# ArtFire.net
KiCad netlist of a schematic drawn in Altium Designer
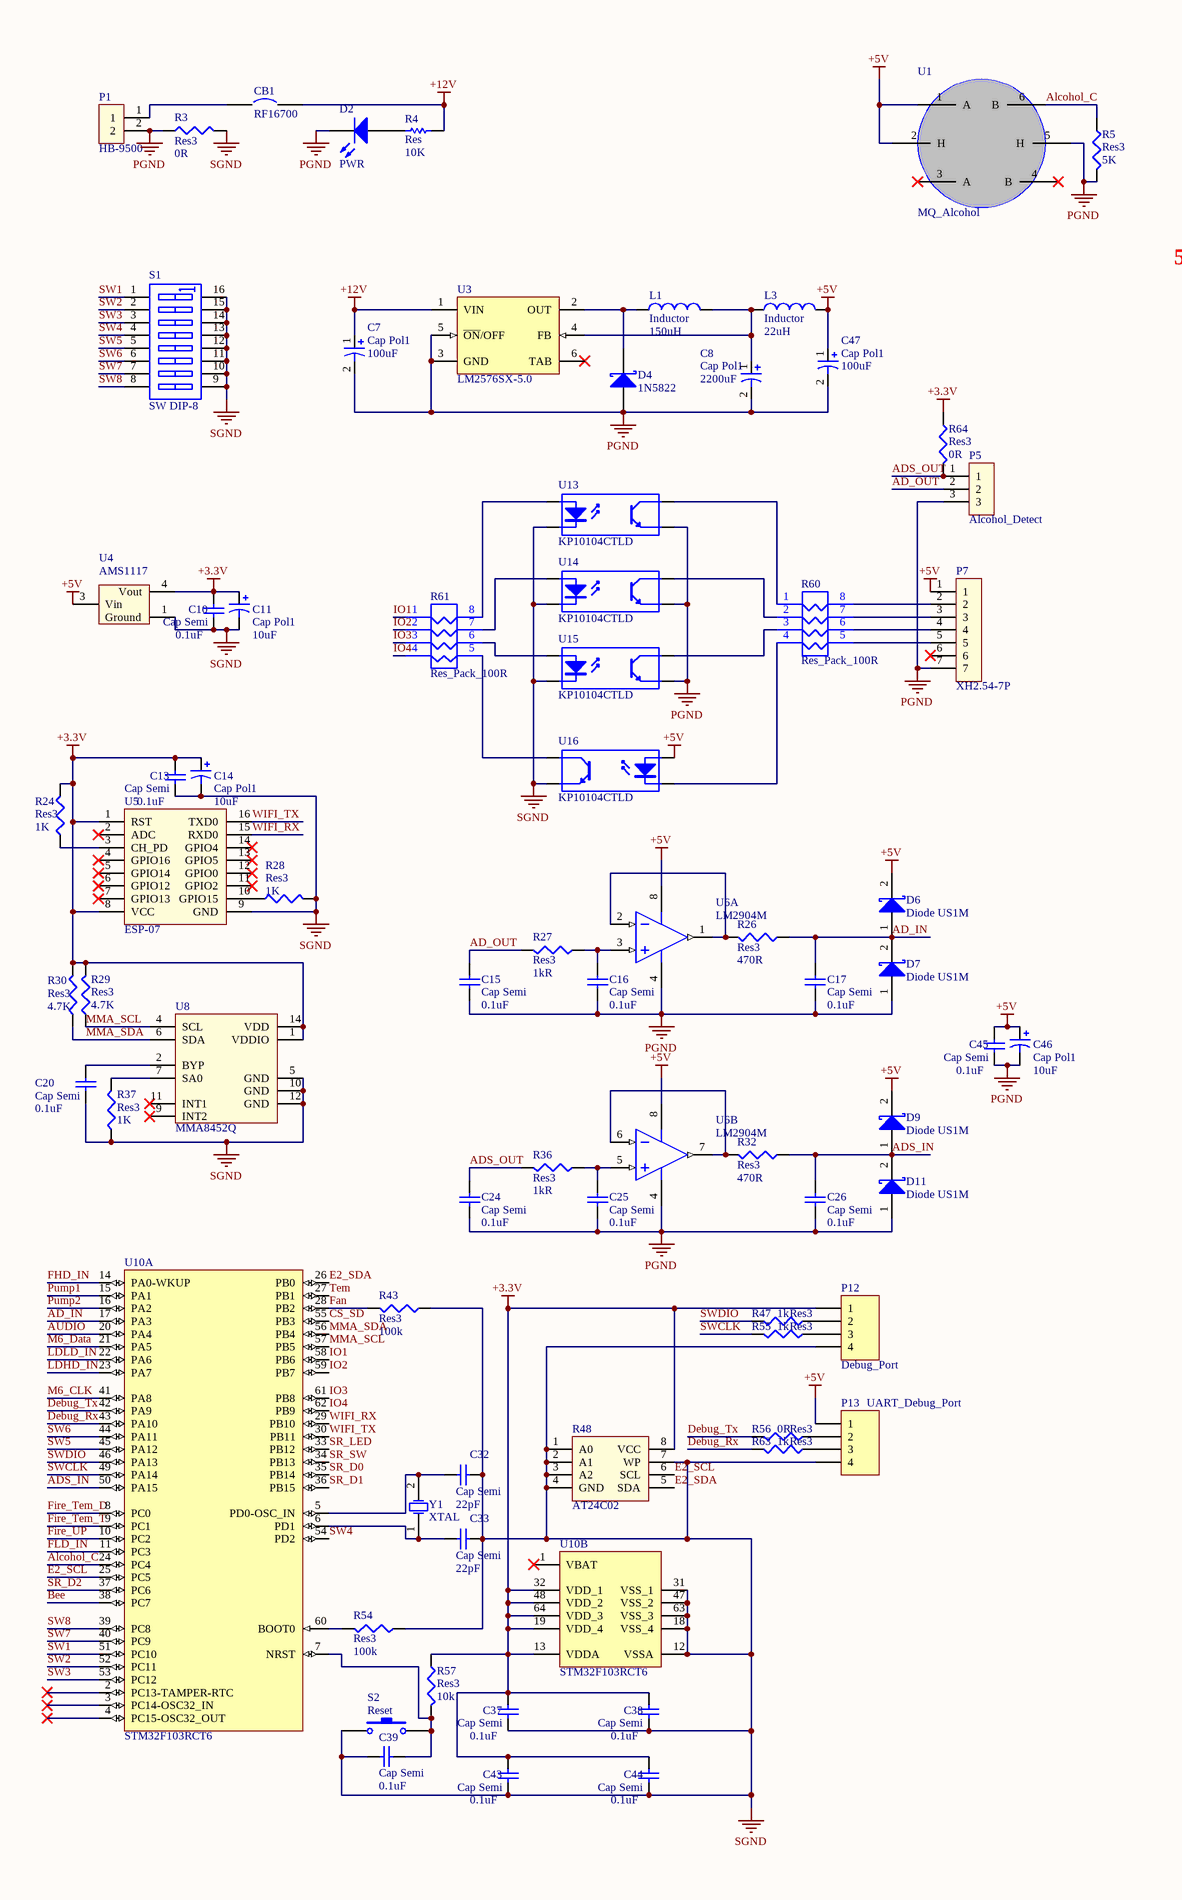
[diagram p0: ArtFire.SchDoc, left]
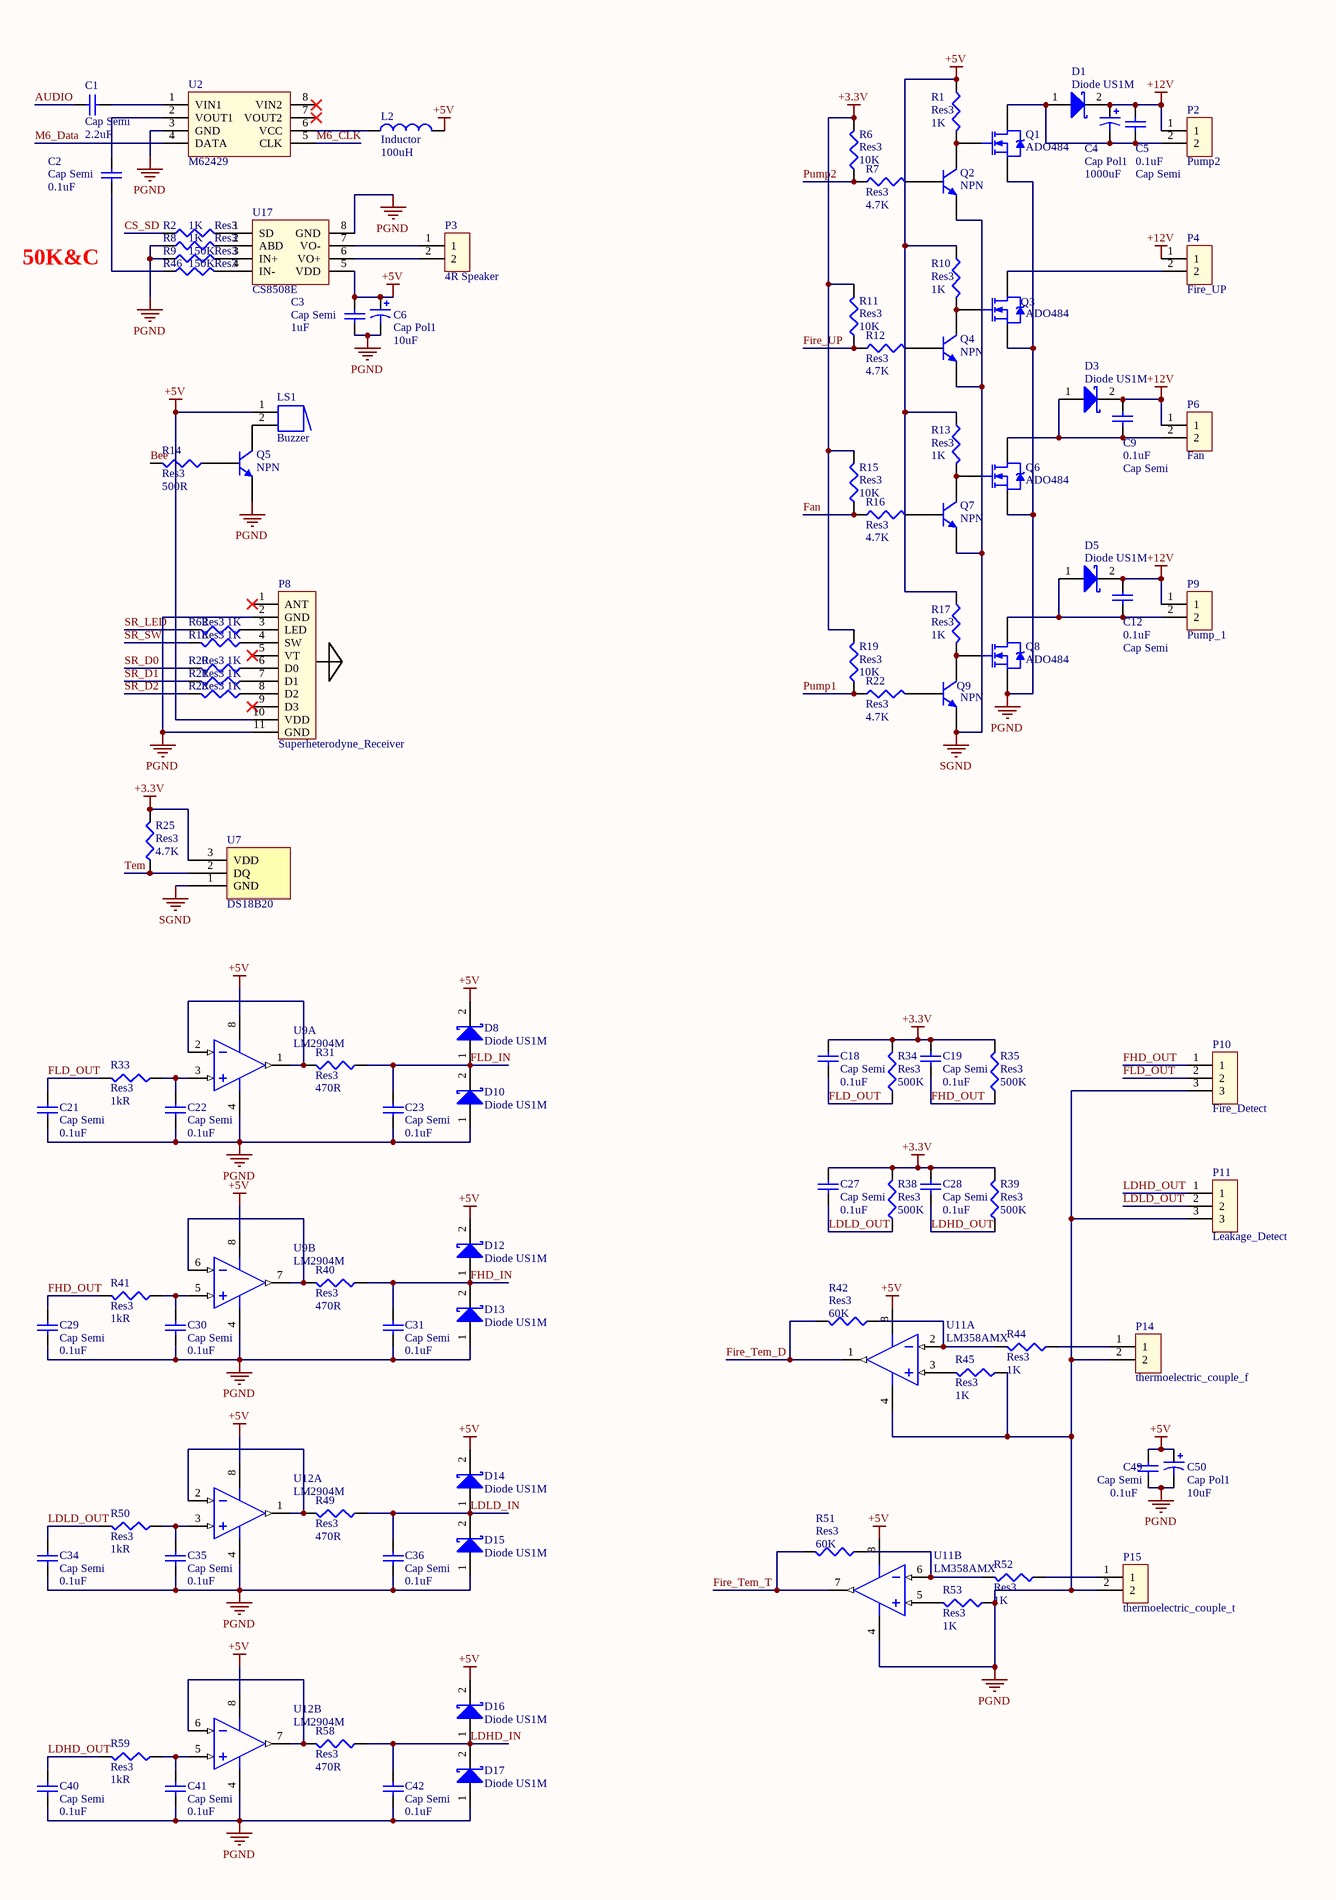
[diagram p1: ArtFire.SchDoc, right]

(export (version "E")
  (design (tool "Eeschema 10.0.6"))
  (components
    (comp (ref "C1")
      (value "Cap Semi")
      (footprint "6-0805_N")
      (description "Capacitor (Semiconductor SIM Model)")
      (fields (field (name "ALTIUM_VALUE") "2.2uF") (field (name "PUBLISHER") "Altium Limited"))
      (libsource (lib "Miscellaneous Devices") (part "Cap Semi"))
    )
    (comp (ref "C2")
      (value "Cap Semi")
      (footprint "6-0805_N")
      (description "Capacitor (Semiconductor SIM Model)")
      (fields (field (name "ALTIUM_VALUE") "0.1uF") (field (name "PUBLISHER") "Altium Limited"))
      (libsource (lib "Miscellaneous Devices") (part "Cap Semi"))
    )
    (comp (ref "C3")
      (value "Cap Semi")
      (footprint "6-0805_N")
      (description "Capacitor (Semiconductor SIM Model)")
      (fields (field (name "ALTIUM_VALUE") "1uF") (field (name "PUBLISHER") "Altium Limited"))
      (libsource (lib "Miscellaneous Devices") (part "Cap Semi"))
    )
    (comp (ref "C4")
      (value "Cap Pol1")
      (footprint "CAP_10*10MM")
      (description "Polarized Capacitor (Radial)")
      (fields (field (name "ALTIUM_VALUE") "1000uF") (field (name "PUBLISHER") "Altium Limited"))
      (libsource (lib "Miscellaneous Devices") (part "Cap Pol1"))
    )
    (comp (ref "C5")
      (value "Cap Semi")
      (footprint "6-0805_N")
      (description "Capacitor (Semiconductor SIM Model)")
      (fields (field (name "ALTIUM_VALUE") "0.1uF") (field (name "PUBLISHER") "Altium Limited"))
      (libsource (lib "Miscellaneous Devices") (part "Cap Semi"))
    )
    (comp (ref "C6")
      (value "Cap Pol1")
      (footprint "Cap_5*4mm")
      (description "Polarized Capacitor (Radial)")
      (fields (field (name "ALTIUM_VALUE") "10uF") (field (name "PUBLISHER") "Altium Limited"))
      (libsource (lib "Miscellaneous Devices") (part "Cap Pol1"))
    )
    (comp (ref "C7")
      (value "Cap Pol1")
      (footprint "CAP_6.3*5.4MM")
      (description "Polarized Capacitor (Radial)")
      (fields (field (name "ALTIUM_VALUE") "100uF") (field (name "PUBLISHER") "Altium Limited"))
      (libsource (lib "") (part "Cap Pol1_1"))
    )
    (comp (ref "C8")
      (value "Cap Pol1")
      (footprint "CAP10_17")
      (description "Polarized Capacitor (Radial)")
      (fields (field (name "ALTIUM_VALUE") "2200uF") (field (name "PUBLISHER") "Altium Limited"))
      (libsource (lib "") (part "Cap Pol1_1"))
    )
    (comp (ref "C9")
      (value "Cap Semi")
      (footprint "6-0805_N")
      (description "Capacitor (Semiconductor SIM Model)")
      (fields (field (name "ALTIUM_VALUE") "0.1uF") (field (name "PUBLISHER") "Altium Limited"))
      (libsource (lib "Miscellaneous Devices") (part "Cap Semi"))
    )
    (comp (ref "C10")
      (value "Cap Semi")
      (footprint "6-0805_N")
      (description "Capacitor (Semiconductor SIM Model)")
      (fields (field (name "ALTIUM_VALUE") "0.1uF") (field (name "PUBLISHER") "Altium Limited"))
      (libsource (lib "Miscellaneous Devices") (part "Cap Semi"))
    )
    (comp (ref "C11")
      (value "Cap Pol1")
      (footprint "Cap_5*4mm")
      (description "Polarized Capacitor (Radial)")
      (fields (field (name "ALTIUM_VALUE") "10uF") (field (name "PUBLISHER") "Altium Limited"))
      (libsource (lib "Miscellaneous Devices") (part "Cap Pol1"))
    )
    (comp (ref "C12")
      (value "Cap Semi")
      (footprint "6-0805_N")
      (description "Capacitor (Semiconductor SIM Model)")
      (fields (field (name "ALTIUM_VALUE") "0.1uF") (field (name "PUBLISHER") "Altium Limited"))
      (libsource (lib "Miscellaneous Devices") (part "Cap Semi"))
    )
    (comp (ref "C13")
      (value "Cap Semi")
      (footprint "6-0805_N")
      (description "Capacitor (Semiconductor SIM Model)")
      (fields (field (name "ALTIUM_VALUE") "0.1uF") (field (name "PUBLISHER") "Altium Limited"))
      (libsource (lib "Miscellaneous Devices") (part "Cap Semi"))
    )
    (comp (ref "C14")
      (value "Cap Pol1")
      (footprint "Cap_5*4mm")
      (description "Polarized Capacitor (Radial)")
      (fields (field (name "ALTIUM_VALUE") "10uF") (field (name "PUBLISHER") "Altium Limited"))
      (libsource (lib "Miscellaneous Devices") (part "Cap Pol1"))
    )
    (comp (ref "C15")
      (value "Cap Semi")
      (footprint "6-0805_N")
      (description "Capacitor (Semiconductor SIM Model)")
      (fields (field (name "ALTIUM_VALUE") "0.1uF") (field (name "PUBLISHER") "Altium Limited"))
      (libsource (lib "Miscellaneous Devices") (part "Cap Semi"))
    )
    (comp (ref "C16")
      (value "Cap Semi")
      (footprint "6-0805_N")
      (description "Capacitor (Semiconductor SIM Model)")
      (fields (field (name "ALTIUM_VALUE") "0.1uF") (field (name "PUBLISHER") "Altium Limited"))
      (libsource (lib "Miscellaneous Devices") (part "Cap Semi"))
    )
    (comp (ref "C17")
      (value "Cap Semi")
      (footprint "6-0805_N")
      (description "Capacitor (Semiconductor SIM Model)")
      (fields (field (name "ALTIUM_VALUE") "0.1uF") (field (name "PUBLISHER") "Altium Limited"))
      (libsource (lib "Miscellaneous Devices") (part "Cap Semi"))
    )
    (comp (ref "C18")
      (value "Cap Semi")
      (footprint "6-0805_N")
      (description "Capacitor (Semiconductor SIM Model)")
      (fields (field (name "ALTIUM_VALUE") "0.1uF") (field (name "PUBLISHER") "Altium Limited"))
      (libsource (lib "Miscellaneous Devices") (part "Cap Semi"))
    )
    (comp (ref "C19")
      (value "Cap Semi")
      (footprint "6-0805_N")
      (description "Capacitor (Semiconductor SIM Model)")
      (fields (field (name "ALTIUM_VALUE") "0.1uF") (field (name "PUBLISHER") "Altium Limited"))
      (libsource (lib "Miscellaneous Devices") (part "Cap Semi"))
    )
    (comp (ref "C20")
      (value "Cap Semi")
      (footprint "6-0805_N")
      (description "Capacitor (Semiconductor SIM Model)")
      (fields (field (name "ALTIUM_VALUE") "0.1uF") (field (name "PUBLISHER") "Altium Limited"))
      (libsource (lib "Miscellaneous Devices") (part "Cap Semi"))
    )
    (comp (ref "C21")
      (value "Cap Semi")
      (footprint "6-0805_N")
      (description "Capacitor (Semiconductor SIM Model)")
      (fields (field (name "ALTIUM_VALUE") "0.1uF") (field (name "PUBLISHER") "Altium Limited"))
      (libsource (lib "Miscellaneous Devices") (part "Cap Semi"))
    )
    (comp (ref "C22")
      (value "Cap Semi")
      (footprint "6-0805_N")
      (description "Capacitor (Semiconductor SIM Model)")
      (fields (field (name "ALTIUM_VALUE") "0.1uF") (field (name "PUBLISHER") "Altium Limited"))
      (libsource (lib "Miscellaneous Devices") (part "Cap Semi"))
    )
    (comp (ref "C23")
      (value "Cap Semi")
      (footprint "6-0805_N")
      (description "Capacitor (Semiconductor SIM Model)")
      (fields (field (name "ALTIUM_VALUE") "0.1uF") (field (name "PUBLISHER") "Altium Limited"))
      (libsource (lib "Miscellaneous Devices") (part "Cap Semi"))
    )
    (comp (ref "C24")
      (value "Cap Semi")
      (footprint "6-0805_N")
      (description "Capacitor (Semiconductor SIM Model)")
      (fields (field (name "ALTIUM_VALUE") "0.1uF") (field (name "PUBLISHER") "Altium Limited"))
      (libsource (lib "Miscellaneous Devices") (part "Cap Semi"))
    )
    (comp (ref "C25")
      (value "Cap Semi")
      (footprint "6-0805_N")
      (description "Capacitor (Semiconductor SIM Model)")
      (fields (field (name "ALTIUM_VALUE") "0.1uF") (field (name "PUBLISHER") "Altium Limited"))
      (libsource (lib "Miscellaneous Devices") (part "Cap Semi"))
    )
    (comp (ref "C26")
      (value "Cap Semi")
      (footprint "6-0805_N")
      (description "Capacitor (Semiconductor SIM Model)")
      (fields (field (name "ALTIUM_VALUE") "0.1uF") (field (name "PUBLISHER") "Altium Limited"))
      (libsource (lib "Miscellaneous Devices") (part "Cap Semi"))
    )
    (comp (ref "C27")
      (value "Cap Semi")
      (footprint "6-0805_N")
      (description "Capacitor (Semiconductor SIM Model)")
      (fields (field (name "ALTIUM_VALUE") "0.1uF") (field (name "PUBLISHER") "Altium Limited"))
      (libsource (lib "Miscellaneous Devices") (part "Cap Semi"))
    )
    (comp (ref "C28")
      (value "Cap Semi")
      (footprint "6-0805_N")
      (description "Capacitor (Semiconductor SIM Model)")
      (fields (field (name "ALTIUM_VALUE") "0.1uF") (field (name "PUBLISHER") "Altium Limited"))
      (libsource (lib "Miscellaneous Devices") (part "Cap Semi"))
    )
    (comp (ref "C29")
      (value "Cap Semi")
      (footprint "6-0805_N")
      (description "Capacitor (Semiconductor SIM Model)")
      (fields (field (name "ALTIUM_VALUE") "0.1uF") (field (name "PUBLISHER") "Altium Limited"))
      (libsource (lib "Miscellaneous Devices") (part "Cap Semi"))
    )
    (comp (ref "C30")
      (value "Cap Semi")
      (footprint "6-0805_N")
      (description "Capacitor (Semiconductor SIM Model)")
      (fields (field (name "ALTIUM_VALUE") "0.1uF") (field (name "PUBLISHER") "Altium Limited"))
      (libsource (lib "Miscellaneous Devices") (part "Cap Semi"))
    )
    (comp (ref "C31")
      (value "Cap Semi")
      (footprint "6-0805_N")
      (description "Capacitor (Semiconductor SIM Model)")
      (fields (field (name "ALTIUM_VALUE") "0.1uF") (field (name "PUBLISHER") "Altium Limited"))
      (libsource (lib "Miscellaneous Devices") (part "Cap Semi"))
    )
    (comp (ref "C32")
      (value "Cap Semi")
      (footprint "6-0805_N")
      (description "Capacitor (Semiconductor SIM Model)")
      (fields (field (name "ALTIUM_VALUE") "22pF") (field (name "PUBLISHER") "Altium Limited"))
      (libsource (lib "Miscellaneous Devices") (part "Cap Semi"))
    )
    (comp (ref "C33")
      (value "Cap Semi")
      (footprint "6-0805_N")
      (description "Capacitor (Semiconductor SIM Model)")
      (fields (field (name "ALTIUM_VALUE") "22pF") (field (name "PUBLISHER") "Altium Limited"))
      (libsource (lib "Miscellaneous Devices") (part "Cap Semi"))
    )
    (comp (ref "C34")
      (value "Cap Semi")
      (footprint "6-0805_N")
      (description "Capacitor (Semiconductor SIM Model)")
      (fields (field (name "ALTIUM_VALUE") "0.1uF") (field (name "PUBLISHER") "Altium Limited"))
      (libsource (lib "Miscellaneous Devices") (part "Cap Semi"))
    )
    (comp (ref "C35")
      (value "Cap Semi")
      (footprint "6-0805_N")
      (description "Capacitor (Semiconductor SIM Model)")
      (fields (field (name "ALTIUM_VALUE") "0.1uF") (field (name "PUBLISHER") "Altium Limited"))
      (libsource (lib "Miscellaneous Devices") (part "Cap Semi"))
    )
    (comp (ref "C36")
      (value "Cap Semi")
      (footprint "6-0805_N")
      (description "Capacitor (Semiconductor SIM Model)")
      (fields (field (name "ALTIUM_VALUE") "0.1uF") (field (name "PUBLISHER") "Altium Limited"))
      (libsource (lib "Miscellaneous Devices") (part "Cap Semi"))
    )
    (comp (ref "C37")
      (value "Cap Semi")
      (footprint "6-0805_N")
      (description "Capacitor (Semiconductor SIM Model)")
      (fields (field (name "ALTIUM_VALUE") "0.1uF") (field (name "PUBLISHER") "Altium Limited"))
      (libsource (lib "Miscellaneous Devices") (part "Cap Semi"))
    )
    (comp (ref "C38")
      (value "Cap Semi")
      (footprint "6-0805_N")
      (description "Capacitor (Semiconductor SIM Model)")
      (fields (field (name "ALTIUM_VALUE") "0.1uF") (field (name "PUBLISHER") "Altium Limited"))
      (libsource (lib "Miscellaneous Devices") (part "Cap Semi"))
    )
    (comp (ref "C39")
      (value "Cap Semi")
      (footprint "6-0805_N")
      (description "Capacitor (Semiconductor SIM Model)")
      (fields (field (name "ALTIUM_VALUE") "0.1uF") (field (name "PUBLISHER") "Altium Limited"))
      (libsource (lib "Miscellaneous Devices") (part "Cap Semi"))
    )
    (comp (ref "C40")
      (value "Cap Semi")
      (footprint "6-0805_N")
      (description "Capacitor (Semiconductor SIM Model)")
      (fields (field (name "ALTIUM_VALUE") "0.1uF") (field (name "PUBLISHER") "Altium Limited"))
      (libsource (lib "Miscellaneous Devices") (part "Cap Semi"))
    )
    (comp (ref "C41")
      (value "Cap Semi")
      (footprint "6-0805_N")
      (description "Capacitor (Semiconductor SIM Model)")
      (fields (field (name "ALTIUM_VALUE") "0.1uF") (field (name "PUBLISHER") "Altium Limited"))
      (libsource (lib "Miscellaneous Devices") (part "Cap Semi"))
    )
    (comp (ref "C42")
      (value "Cap Semi")
      (footprint "6-0805_N")
      (description "Capacitor (Semiconductor SIM Model)")
      (fields (field (name "ALTIUM_VALUE") "0.1uF") (field (name "PUBLISHER") "Altium Limited"))
      (libsource (lib "Miscellaneous Devices") (part "Cap Semi"))
    )
    (comp (ref "C43")
      (value "Cap Semi")
      (footprint "6-0805_N")
      (description "Capacitor (Semiconductor SIM Model)")
      (fields (field (name "ALTIUM_VALUE") "0.1uF") (field (name "PUBLISHER") "Altium Limited"))
      (libsource (lib "Miscellaneous Devices") (part "Cap Semi"))
    )
    (comp (ref "C44")
      (value "Cap Semi")
      (footprint "6-0805_N")
      (description "Capacitor (Semiconductor SIM Model)")
      (fields (field (name "ALTIUM_VALUE") "0.1uF") (field (name "PUBLISHER") "Altium Limited"))
      (libsource (lib "Miscellaneous Devices") (part "Cap Semi"))
    )
    (comp (ref "C45")
      (value "Cap Semi")
      (footprint "6-0805_N")
      (description "Capacitor (Semiconductor SIM Model)")
      (fields (field (name "ALTIUM_VALUE") "0.1uF") (field (name "PUBLISHER") "Altium Limited"))
      (libsource (lib "Miscellaneous Devices") (part "Cap Semi"))
    )
    (comp (ref "C46")
      (value "Cap Pol1")
      (footprint "Cap_5*4mm")
      (description "Polarized Capacitor (Radial)")
      (fields (field (name "ALTIUM_VALUE") "10uF") (field (name "PUBLISHER") "Altium Limited"))
      (libsource (lib "Miscellaneous Devices") (part "Cap Pol1"))
    )
    (comp (ref "C47")
      (value "Cap Pol1")
      (footprint "CAP_6.3*5.4MM")
      (description "Polarized Capacitor (Radial)")
      (fields (field (name "ALTIUM_VALUE") "100uF") (field (name "PUBLISHER") "Altium Limited"))
      (libsource (lib "") (part "Cap Pol1_1"))
    )
    (comp (ref "C49")
      (value "Cap Semi")
      (footprint "6-0805_N")
      (description "Capacitor (Semiconductor SIM Model)")
      (fields (field (name "ALTIUM_VALUE") "0.1uF") (field (name "PUBLISHER") "Altium Limited"))
      (libsource (lib "Miscellaneous Devices") (part "Cap Semi"))
    )
    (comp (ref "C50")
      (value "Cap Pol1")
      (footprint "Cap_5*4mm")
      (description "Polarized Capacitor (Radial)")
      (fields (field (name "ALTIUM_VALUE") "10uF") (field (name "PUBLISHER") "Altium Limited"))
      (libsource (lib "Miscellaneous Devices") (part "Cap Pol1"))
    )
    (comp (ref "CB1")
      (value "RF16700")
      (footprint "SPST-2")
      (description "Circuit Breaker")
      (fields (field (name "PUBLISHER") "Altium Limited"))
      (libsource (lib "Miscellaneous Devices") (part "Circuit Breaker"))
    )
    (comp (ref "D1")
      (value "Diode US1M")
      (footprint "US1M")
      (description "Silicon RF Schottky Diode for Mixer Applications in the VHF/UHF Range")
      (fields (field (name "PUBLISHER") "Altium Limited"))
      (libsource (lib "Miscellaneous Devices") (part "Diode BAT17"))
    )
    (comp (ref "D2")
      (value "PWR")
      (footprint "6-0805_N")
      (description "Typical INFRARED GaAs LED")
      (fields (field (name "PUBLISHER") "Altium Limited"))
      (libsource (lib "Miscellaneous Devices") (part "LED0"))
    )
    (comp (ref "D3")
      (value "Diode US1M")
      (footprint "US1M")
      (description "Silicon RF Schottky Diode for Mixer Applications in the VHF/UHF Range")
      (fields (field (name "PUBLISHER") "Altium Limited"))
      (libsource (lib "Miscellaneous Devices") (part "Diode BAT17"))
    )
    (comp (ref "D4")
      (value "1N5822")
      (footprint "US1M")
      (description "Silicon RF Schottky Diode for Mixer Applications in the VHF/UHF Range")
      (fields (field (name "PUBLISHER") "Altium Limited"))
      (libsource (lib "") (part "Diode BAT17_1"))
    )
    (comp (ref "D5")
      (value "Diode US1M")
      (footprint "US1M")
      (description "Silicon RF Schottky Diode for Mixer Applications in the VHF/UHF Range")
      (fields (field (name "PUBLISHER") "Altium Limited"))
      (libsource (lib "Miscellaneous Devices") (part "Diode BAT17"))
    )
    (comp (ref "D6")
      (value "Diode US1M")
      (footprint "US1M")
      (description "Silicon RF Schottky Diode for Mixer Applications in the VHF/UHF Range")
      (fields (field (name "PUBLISHER") "Altium Limited"))
      (libsource (lib "Miscellaneous Devices") (part "Diode BAT17"))
    )
    (comp (ref "D7")
      (value "Diode US1M")
      (footprint "US1M")
      (description "Silicon RF Schottky Diode for Mixer Applications in the VHF/UHF Range")
      (fields (field (name "PUBLISHER") "Altium Limited"))
      (libsource (lib "Miscellaneous Devices") (part "Diode BAT17"))
    )
    (comp (ref "D8")
      (value "Diode US1M")
      (footprint "US1M")
      (description "Silicon RF Schottky Diode for Mixer Applications in the VHF/UHF Range")
      (fields (field (name "PUBLISHER") "Altium Limited"))
      (libsource (lib "Miscellaneous Devices") (part "Diode BAT17"))
    )
    (comp (ref "D9")
      (value "Diode US1M")
      (footprint "US1M")
      (description "Silicon RF Schottky Diode for Mixer Applications in the VHF/UHF Range")
      (fields (field (name "PUBLISHER") "Altium Limited"))
      (libsource (lib "Miscellaneous Devices") (part "Diode BAT17"))
    )
    (comp (ref "D10")
      (value "Diode US1M")
      (footprint "US1M")
      (description "Silicon RF Schottky Diode for Mixer Applications in the VHF/UHF Range")
      (fields (field (name "PUBLISHER") "Altium Limited"))
      (libsource (lib "Miscellaneous Devices") (part "Diode BAT17"))
    )
    (comp (ref "D11")
      (value "Diode US1M")
      (footprint "US1M")
      (description "Silicon RF Schottky Diode for Mixer Applications in the VHF/UHF Range")
      (fields (field (name "PUBLISHER") "Altium Limited"))
      (libsource (lib "Miscellaneous Devices") (part "Diode BAT17"))
    )
    (comp (ref "D12")
      (value "Diode US1M")
      (footprint "US1M")
      (description "Silicon RF Schottky Diode for Mixer Applications in the VHF/UHF Range")
      (fields (field (name "PUBLISHER") "Altium Limited"))
      (libsource (lib "Miscellaneous Devices") (part "Diode BAT17"))
    )
    (comp (ref "D13")
      (value "Diode US1M")
      (footprint "US1M")
      (description "Silicon RF Schottky Diode for Mixer Applications in the VHF/UHF Range")
      (fields (field (name "PUBLISHER") "Altium Limited"))
      (libsource (lib "Miscellaneous Devices") (part "Diode BAT17"))
    )
    (comp (ref "D14")
      (value "Diode US1M")
      (footprint "US1M")
      (description "Silicon RF Schottky Diode for Mixer Applications in the VHF/UHF Range")
      (fields (field (name "PUBLISHER") "Altium Limited"))
      (libsource (lib "Miscellaneous Devices") (part "Diode BAT17"))
    )
    (comp (ref "D15")
      (value "Diode US1M")
      (footprint "US1M")
      (description "Silicon RF Schottky Diode for Mixer Applications in the VHF/UHF Range")
      (fields (field (name "PUBLISHER") "Altium Limited"))
      (libsource (lib "Miscellaneous Devices") (part "Diode BAT17"))
    )
    (comp (ref "D16")
      (value "Diode US1M")
      (footprint "US1M")
      (description "Silicon RF Schottky Diode for Mixer Applications in the VHF/UHF Range")
      (fields (field (name "PUBLISHER") "Altium Limited"))
      (libsource (lib "Miscellaneous Devices") (part "Diode BAT17"))
    )
    (comp (ref "D17")
      (value "Diode US1M")
      (footprint "US1M")
      (description "Silicon RF Schottky Diode for Mixer Applications in the VHF/UHF Range")
      (fields (field (name "PUBLISHER") "Altium Limited"))
      (libsource (lib "Miscellaneous Devices") (part "Diode BAT17"))
    )
    (comp (ref "L1")
      (value "Inductor")
      (footprint "CDRH127")
      (fields (field (name "ALTIUM_VALUE") "150uH") (field (name "PUBLISHER") "Altium Limited"))
      (libsource (lib "Miscellaneous Devices") (part "Inductor"))
    )
    (comp (ref "L2")
      (value "Inductor")
      (footprint "6-0805_L")
      (fields (field (name "ALTIUM_VALUE") "100uH") (field (name "PUBLISHER") "Altium Limited"))
      (libsource (lib "Miscellaneous Devices") (part "Inductor"))
    )
    (comp (ref "L3")
      (value "Inductor")
      (footprint "IND_0630")
      (fields (field (name "ALTIUM_VALUE") "22uH") (field (name "PUBLISHER") "Altium Limited"))
      (libsource (lib "Miscellaneous Devices") (part "Inductor"))
    )
    (comp (ref "LS1")
      (value "Buzzer")
      (footprint "BUZZER")
      (description "Magnetic Transducer Buzzer")
      (fields (field (name "PUBLISHER") "Altium Limited"))
      (libsource (lib "Miscellaneous Devices") (part "Buzzer"))
    )
    (comp (ref "P1")
      (value "HB-9500")
      (footprint "HB-9500")
      (description "High current connector")
      (libsource (lib "Simon'Library") (part "HB-9500"))
    )
    (comp (ref "P2") (value "Pump2") (footprint "CH3.96_2P") (libsource (lib "CH3.96") (part "CH3.96_2P")))
    (comp (ref "P3")
      (value "4R Speaker")
      (footprint "XH2.54-2P")
      (libsource (lib "XH2.54") (part "XH2.54-2P"))
    )
    (comp (ref "P4") (value "Fire_UP") (footprint "KF7.62-2P") (libsource (lib "KF3.96") (part "KF3.96")))
    (comp (ref "P5")
      (value "Alcohol_Detect")
      (footprint "XH2.54-3P")
      (libsource (lib "XH2.54") (part "XH2.54-3P"))
    )
    (comp (ref "P6") (value "Fan") (footprint "XH2.54-2P") (libsource (lib "XH2.54") (part "XH2.54-2P")))
    (comp (ref "P7")
      (value "XH2.54-7P")
      (footprint "XH2.54-7P")
      (libsource (lib "XH2.54") (part "XH2.54-7P"))
    )
    (comp (ref "P8")
      (value "Superheterodyne_Receiver")
      (footprint "Sperheterodyne_Receiver")
      (libsource (lib "Simon'Library") (part "Superheterodyne_Receiver"))
    )
    (comp (ref "P9") (value "Pump_1") (footprint "CH3.96_2P") (libsource (lib "CH3.96") (part "CH3.96_2P")))
    (comp (ref "P10")
      (value "Fire_Detect")
      (footprint "CH3.96_3P")
      (libsource (lib "CH3.96") (part "CH3.96_3P"))
    )
    (comp (ref "P11")
      (value "Leakage_Detect")
      (footprint "XH2.54-3P")
      (libsource (lib "XH2.54") (part "XH2.54-3P"))
    )
    (comp (ref "P12")
      (value "Debug_Port")
      (footprint "HDR1X4")
      (description "Header, 4-Pin")
      (fields (field (name "PUBLISHER") "Altium Limited"))
      (libsource (lib "Miscellaneous Connectors") (part "Header 4"))
    )
    (comp (ref "P13")
      (value "UART_Debug_Port")
      (footprint "HDR1X4")
      (description "Header, 4-Pin")
      (fields (field (name "PUBLISHER") "Altium Limited"))
      (libsource (lib "Miscellaneous Connectors") (part "Header 4"))
    )
    (comp (ref "P14")
      (value "thermoelectric_couple_f")
      (footprint "KF7.62-2P")
      (libsource (lib "KF3.96") (part "KF3.96"))
    )
    (comp (ref "P15")
      (value "thermoelectric_couple_t")
      (footprint "KF7.62-2P")
      (libsource (lib "KF3.96") (part "KF3.96"))
    )
    (comp (ref "Q1")
      (value "ADO484")
      (footprint "DPAK_AOD484")
      (description "N-Channel Power MOSFET")
      (fields (field (name "PUBLISHER") "Altium Limited"))
      (libsource (lib "Miscellaneous Devices") (part "NMOS-2"))
    )
    (comp (ref "Q2")
      (value "NPN")
      (footprint "SOT-23_N")
      (description "NPN Bipolar Transistor")
      (fields (field (name "PUBLISHER") "Altium Limited"))
      (libsource (lib "Miscellaneous Devices") (part "NPN"))
    )
    (comp (ref "Q3")
      (value "ADO484")
      (footprint "DPAK_AOD484")
      (description "N-Channel Power MOSFET")
      (fields (field (name "PUBLISHER") "Altium Limited"))
      (libsource (lib "Miscellaneous Devices") (part "NMOS-2"))
    )
    (comp (ref "Q4")
      (value "NPN")
      (footprint "SOT-23_N")
      (description "NPN Bipolar Transistor")
      (fields (field (name "PUBLISHER") "Altium Limited"))
      (libsource (lib "Miscellaneous Devices") (part "NPN"))
    )
    (comp (ref "Q5")
      (value "NPN")
      (footprint "SOT-23_N")
      (description "NPN Bipolar Transistor")
      (fields (field (name "PUBLISHER") "Altium Limited"))
      (libsource (lib "Miscellaneous Devices") (part "NPN"))
    )
    (comp (ref "Q6")
      (value "ADO484")
      (footprint "DPAK_AOD484")
      (description "N-Channel Power MOSFET")
      (fields (field (name "PUBLISHER") "Altium Limited"))
      (libsource (lib "Miscellaneous Devices") (part "NMOS-2"))
    )
    (comp (ref "Q7")
      (value "NPN")
      (footprint "SOT-23_N")
      (description "NPN Bipolar Transistor")
      (fields (field (name "PUBLISHER") "Altium Limited"))
      (libsource (lib "Miscellaneous Devices") (part "NPN"))
    )
    (comp (ref "Q8")
      (value "ADO484")
      (footprint "DPAK_AOD484")
      (description "N-Channel Power MOSFET")
      (fields (field (name "PUBLISHER") "Altium Limited"))
      (libsource (lib "Miscellaneous Devices") (part "NMOS-2"))
    )
    (comp (ref "Q9")
      (value "NPN")
      (footprint "SOT-23_N")
      (description "NPN Bipolar Transistor")
      (fields (field (name "PUBLISHER") "Altium Limited"))
      (libsource (lib "Miscellaneous Devices") (part "NPN"))
    )
    (comp (ref "R1")
      (value "Res3")
      (footprint "6-0805_N")
      (description "Resistor")
      (fields (field (name "ALTIUM_VALUE") "1K") (field (name "PUBLISHER") "Altium Limited"))
      (libsource (lib "Miscellaneous Devices") (part "Res3"))
    )
    (comp (ref "R2")
      (value "Res3")
      (footprint "6-0805_N")
      (description "Resistor")
      (fields (field (name "ALTIUM_VALUE") "1K") (field (name "PUBLISHER") "Altium Limited"))
      (libsource (lib "Miscellaneous Devices") (part "Res3"))
    )
    (comp (ref "R3")
      (value "Res3")
      (footprint "6-0805_N")
      (description "Resistor")
      (fields (field (name "ALTIUM_VALUE") "0R") (field (name "PUBLISHER") "Altium Limited"))
      (libsource (lib "Miscellaneous Devices") (part "Res3"))
    )
    (comp (ref "R4")
      (value "Res")
      (footprint "6-0805_N")
      (description "Resistor")
      (fields (field (name "ALTIUM_VALUE") "10K") (field (name "PUBLISHER") "Altium Limited"))
      (libsource (lib "Miscellaneous Devices") (part "Res1"))
    )
    (comp (ref "R5")
      (value "Res3")
      (footprint "6-0805_N")
      (description "Resistor")
      (fields (field (name "ALTIUM_VALUE") "5K") (field (name "PUBLISHER") "Altium Limited"))
      (libsource (lib "Miscellaneous Devices") (part "Res3"))
    )
    (comp (ref "R6")
      (value "Res3")
      (footprint "6-0805_N")
      (description "Resistor")
      (fields (field (name "ALTIUM_VALUE") "10K") (field (name "PUBLISHER") "Altium Limited"))
      (libsource (lib "Miscellaneous Devices") (part "Res3"))
    )
    (comp (ref "R7")
      (value "Res3")
      (footprint "6-0805_N")
      (description "Resistor")
      (fields (field (name "ALTIUM_VALUE") "4.7K") (field (name "PUBLISHER") "Altium Limited"))
      (libsource (lib "Miscellaneous Devices") (part "Res3"))
    )
    (comp (ref "R8")
      (value "Res3")
      (footprint "6-0805_N")
      (description "Resistor")
      (fields (field (name "ALTIUM_VALUE") "1K") (field (name "PUBLISHER") "Altium Limited"))
      (libsource (lib "Miscellaneous Devices") (part "Res3"))
    )
    (comp (ref "R9")
      (value "Res3")
      (footprint "6-0805_N")
      (description "Resistor")
      (fields (field (name "ALTIUM_VALUE") "150K") (field (name "PUBLISHER") "Altium Limited"))
      (libsource (lib "Miscellaneous Devices") (part "Res3"))
    )
    (comp (ref "R10")
      (value "Res3")
      (footprint "6-0805_N")
      (description "Resistor")
      (fields (field (name "ALTIUM_VALUE") "1K") (field (name "PUBLISHER") "Altium Limited"))
      (libsource (lib "Miscellaneous Devices") (part "Res3"))
    )
    (comp (ref "R11")
      (value "Res3")
      (footprint "6-0805_N")
      (description "Resistor")
      (fields (field (name "ALTIUM_VALUE") "10K") (field (name "PUBLISHER") "Altium Limited"))
      (libsource (lib "Miscellaneous Devices") (part "Res3"))
    )
    (comp (ref "R12")
      (value "Res3")
      (footprint "6-0805_N")
      (description "Resistor")
      (fields (field (name "ALTIUM_VALUE") "4.7K") (field (name "PUBLISHER") "Altium Limited"))
      (libsource (lib "Miscellaneous Devices") (part "Res3"))
    )
    (comp (ref "R13")
      (value "Res3")
      (footprint "6-0805_N")
      (description "Resistor")
      (fields (field (name "ALTIUM_VALUE") "1K") (field (name "PUBLISHER") "Altium Limited"))
      (libsource (lib "Miscellaneous Devices") (part "Res3"))
    )
    (comp (ref "R14")
      (value "Res3")
      (footprint "6-0805_N")
      (description "Resistor")
      (fields (field (name "ALTIUM_VALUE") "500R") (field (name "PUBLISHER") "Altium Limited"))
      (libsource (lib "Miscellaneous Devices") (part "Res3"))
    )
    (comp (ref "R15")
      (value "Res3")
      (footprint "6-0805_N")
      (description "Resistor")
      (fields (field (name "ALTIUM_VALUE") "10K") (field (name "PUBLISHER") "Altium Limited"))
      (libsource (lib "Miscellaneous Devices") (part "Res3"))
    )
    (comp (ref "R16")
      (value "Res3")
      (footprint "6-0805_N")
      (description "Resistor")
      (fields (field (name "ALTIUM_VALUE") "4.7K") (field (name "PUBLISHER") "Altium Limited"))
      (libsource (lib "Miscellaneous Devices") (part "Res3"))
    )
    (comp (ref "R17")
      (value "Res3")
      (footprint "6-0805_N")
      (description "Resistor")
      (fields (field (name "ALTIUM_VALUE") "1K") (field (name "PUBLISHER") "Altium Limited"))
      (libsource (lib "Miscellaneous Devices") (part "Res3"))
    )
    (comp (ref "R18")
      (value "Res3")
      (footprint "6-0805_N")
      (description "Resistor")
      (fields (field (name "ALTIUM_VALUE") "1K") (field (name "PUBLISHER") "Altium Limited"))
      (libsource (lib "Miscellaneous Devices") (part "Res3"))
    )
    (comp (ref "R19")
      (value "Res3")
      (footprint "6-0805_N")
      (description "Resistor")
      (fields (field (name "ALTIUM_VALUE") "10K") (field (name "PUBLISHER") "Altium Limited"))
      (libsource (lib "Miscellaneous Devices") (part "Res3"))
    )
    (comp (ref "R20")
      (value "Res3")
      (footprint "6-0805_N")
      (description "Resistor")
      (fields (field (name "ALTIUM_VALUE") "1K") (field (name "PUBLISHER") "Altium Limited"))
      (libsource (lib "Miscellaneous Devices") (part "Res3"))
    )
    (comp (ref "R21")
      (value "Res3")
      (footprint "6-0805_N")
      (description "Resistor")
      (fields (field (name "ALTIUM_VALUE") "1K") (field (name "PUBLISHER") "Altium Limited"))
      (libsource (lib "Miscellaneous Devices") (part "Res3"))
    )
    (comp (ref "R22")
      (value "Res3")
      (footprint "6-0805_N")
      (description "Resistor")
      (fields (field (name "ALTIUM_VALUE") "4.7K") (field (name "PUBLISHER") "Altium Limited"))
      (libsource (lib "Miscellaneous Devices") (part "Res3"))
    )
    (comp (ref "R23")
      (value "Res3")
      (footprint "6-0805_N")
      (description "Resistor")
      (fields (field (name "ALTIUM_VALUE") "1K") (field (name "PUBLISHER") "Altium Limited"))
      (libsource (lib "Miscellaneous Devices") (part "Res3"))
    )
    (comp (ref "R24")
      (value "Res3")
      (footprint "6-0805_N")
      (description "Resistor")
      (fields (field (name "ALTIUM_VALUE") "1K") (field (name "PUBLISHER") "Altium Limited"))
      (libsource (lib "Miscellaneous Devices") (part "Res3"))
    )
    (comp (ref "R25")
      (value "Res3")
      (footprint "6-0805_N")
      (description "Resistor")
      (fields (field (name "ALTIUM_VALUE") "4.7K") (field (name "PUBLISHER") "Altium Limited"))
      (libsource (lib "Miscellaneous Devices") (part "Res3"))
    )
    (comp (ref "R26")
      (value "Res3")
      (footprint "6-0805_N")
      (description "Resistor")
      (fields (field (name "ALTIUM_VALUE") "470R") (field (name "PUBLISHER") "Altium Limited"))
      (libsource (lib "Miscellaneous Devices") (part "Res3"))
    )
    (comp (ref "R27")
      (value "Res3")
      (footprint "6-0805_N")
      (description "Resistor")
      (fields (field (name "ALTIUM_VALUE") "1kR") (field (name "PUBLISHER") "Altium Limited"))
      (libsource (lib "Miscellaneous Devices") (part "Res3"))
    )
    (comp (ref "R28")
      (value "Res3")
      (footprint "6-0805_N")
      (description "Resistor")
      (fields (field (name "ALTIUM_VALUE") "1K") (field (name "PUBLISHER") "Altium Limited"))
      (libsource (lib "Miscellaneous Devices") (part "Res3"))
    )
    (comp (ref "R29")
      (value "Res3")
      (footprint "6-0805_N")
      (description "Resistor")
      (fields (field (name "ALTIUM_VALUE") "4.7K") (field (name "PUBLISHER") "Altium Limited"))
      (libsource (lib "Miscellaneous Devices") (part "Res3"))
    )
    (comp (ref "R30")
      (value "Res3")
      (footprint "6-0805_N")
      (description "Resistor")
      (fields (field (name "ALTIUM_VALUE") "4.7K") (field (name "PUBLISHER") "Altium Limited"))
      (libsource (lib "Miscellaneous Devices") (part "Res3"))
    )
    (comp (ref "R31")
      (value "Res3")
      (footprint "6-0805_N")
      (description "Resistor")
      (fields (field (name "ALTIUM_VALUE") "470R") (field (name "PUBLISHER") "Altium Limited"))
      (libsource (lib "Miscellaneous Devices") (part "Res3"))
    )
    (comp (ref "R32")
      (value "Res3")
      (footprint "6-0805_N")
      (description "Resistor")
      (fields (field (name "ALTIUM_VALUE") "470R") (field (name "PUBLISHER") "Altium Limited"))
      (libsource (lib "Miscellaneous Devices") (part "Res3"))
    )
    (comp (ref "R33")
      (value "Res3")
      (footprint "6-0805_N")
      (description "Resistor")
      (fields (field (name "ALTIUM_VALUE") "1kR") (field (name "PUBLISHER") "Altium Limited"))
      (libsource (lib "Miscellaneous Devices") (part "Res3"))
    )
    (comp (ref "R34")
      (value "Res3")
      (footprint "6-0805_N")
      (description "Resistor")
      (fields (field (name "ALTIUM_VALUE") "500K") (field (name "PUBLISHER") "Altium Limited"))
      (libsource (lib "Miscellaneous Devices") (part "Res3"))
    )
    (comp (ref "R35")
      (value "Res3")
      (footprint "6-0805_N")
      (description "Resistor")
      (fields (field (name "ALTIUM_VALUE") "500K") (field (name "PUBLISHER") "Altium Limited"))
      (libsource (lib "Miscellaneous Devices") (part "Res3"))
    )
    (comp (ref "R36")
      (value "Res3")
      (footprint "6-0805_N")
      (description "Resistor")
      (fields (field (name "ALTIUM_VALUE") "1kR") (field (name "PUBLISHER") "Altium Limited"))
      (libsource (lib "Miscellaneous Devices") (part "Res3"))
    )
    (comp (ref "R37")
      (value "Res3")
      (footprint "6-0805_N")
      (description "Resistor")
      (fields (field (name "ALTIUM_VALUE") "1K") (field (name "PUBLISHER") "Altium Limited"))
      (libsource (lib "Miscellaneous Devices") (part "Res3"))
    )
    (comp (ref "R38")
      (value "Res3")
      (footprint "6-0805_N")
      (description "Resistor")
      (fields (field (name "ALTIUM_VALUE") "500K") (field (name "PUBLISHER") "Altium Limited"))
      (libsource (lib "Miscellaneous Devices") (part "Res3"))
    )
    (comp (ref "R39")
      (value "Res3")
      (footprint "6-0805_N")
      (description "Resistor")
      (fields (field (name "ALTIUM_VALUE") "500K") (field (name "PUBLISHER") "Altium Limited"))
      (libsource (lib "Miscellaneous Devices") (part "Res3"))
    )
    (comp (ref "R40")
      (value "Res3")
      (footprint "6-0805_N")
      (description "Resistor")
      (fields (field (name "ALTIUM_VALUE") "470R") (field (name "PUBLISHER") "Altium Limited"))
      (libsource (lib "Miscellaneous Devices") (part "Res3"))
    )
    (comp (ref "R41")
      (value "Res3")
      (footprint "6-0805_N")
      (description "Resistor")
      (fields (field (name "ALTIUM_VALUE") "1kR") (field (name "PUBLISHER") "Altium Limited"))
      (libsource (lib "Miscellaneous Devices") (part "Res3"))
    )
    (comp (ref "R42")
      (value "Res3")
      (footprint "6-0805_N")
      (description "Resistor")
      (fields (field (name "ALTIUM_VALUE") "60K") (field (name "PUBLISHER") "Altium Limited"))
      (libsource (lib "Miscellaneous Devices") (part "Res3"))
    )
    (comp (ref "R43")
      (value "Res3")
      (footprint "6-0805_N")
      (description "Resistor")
      (fields (field (name "ALTIUM_VALUE") "100k") (field (name "PUBLISHER") "Altium Limited"))
      (libsource (lib "Miscellaneous Devices") (part "Res3"))
    )
    (comp (ref "R44")
      (value "Res3")
      (footprint "6-0805_N")
      (description "Resistor")
      (fields (field (name "ALTIUM_VALUE") "1K") (field (name "PUBLISHER") "Altium Limited"))
      (libsource (lib "Miscellaneous Devices") (part "Res3"))
    )
    (comp (ref "R45")
      (value "Res3")
      (footprint "6-0805_N")
      (description "Resistor")
      (fields (field (name "ALTIUM_VALUE") "1K") (field (name "PUBLISHER") "Altium Limited"))
      (libsource (lib "Miscellaneous Devices") (part "Res3"))
    )
    (comp (ref "R46")
      (value "Res3")
      (footprint "6-0805_N")
      (description "Resistor")
      (fields (field (name "ALTIUM_VALUE") "150K") (field (name "PUBLISHER") "Altium Limited"))
      (libsource (lib "Miscellaneous Devices") (part "Res3"))
    )
    (comp (ref "R47")
      (value "Res3")
      (footprint "6-0805_N")
      (description "Resistor")
      (fields (field (name "ALTIUM_VALUE") "1k") (field (name "PUBLISHER") "Altium Limited"))
      (libsource (lib "Miscellaneous Devices") (part "Res3"))
    )
    (comp (ref "R48")
      (value "AT24C02")
      (footprint "SOP8_TDA2822")
      (libsource (lib "Simon'Library") (part "AT24C02"))
    )
    (comp (ref "R49")
      (value "Res3")
      (footprint "6-0805_N")
      (description "Resistor")
      (fields (field (name "ALTIUM_VALUE") "470R") (field (name "PUBLISHER") "Altium Limited"))
      (libsource (lib "Miscellaneous Devices") (part "Res3"))
    )
    (comp (ref "R50")
      (value "Res3")
      (footprint "6-0805_N")
      (description "Resistor")
      (fields (field (name "ALTIUM_VALUE") "1kR") (field (name "PUBLISHER") "Altium Limited"))
      (libsource (lib "Miscellaneous Devices") (part "Res3"))
    )
    (comp (ref "R51")
      (value "Res3")
      (footprint "6-0805_N")
      (description "Resistor")
      (fields (field (name "ALTIUM_VALUE") "60K") (field (name "PUBLISHER") "Altium Limited"))
      (libsource (lib "Miscellaneous Devices") (part "Res3"))
    )
    (comp (ref "R52")
      (value "Res3")
      (footprint "6-0805_N")
      (description "Resistor")
      (fields (field (name "ALTIUM_VALUE") "1K") (field (name "PUBLISHER") "Altium Limited"))
      (libsource (lib "Miscellaneous Devices") (part "Res3"))
    )
    (comp (ref "R53")
      (value "Res3")
      (footprint "6-0805_N")
      (description "Resistor")
      (fields (field (name "ALTIUM_VALUE") "1K") (field (name "PUBLISHER") "Altium Limited"))
      (libsource (lib "Miscellaneous Devices") (part "Res3"))
    )
    (comp (ref "R54")
      (value "Res3")
      (footprint "6-0805_N")
      (description "Resistor")
      (fields (field (name "ALTIUM_VALUE") "100k") (field (name "PUBLISHER") "Altium Limited"))
      (libsource (lib "Miscellaneous Devices") (part "Res3"))
    )
    (comp (ref "R55")
      (value "Res3")
      (footprint "6-0805_N")
      (description "Resistor")
      (fields (field (name "ALTIUM_VALUE") "1k") (field (name "PUBLISHER") "Altium Limited"))
      (libsource (lib "Miscellaneous Devices") (part "Res3"))
    )
    (comp (ref "R56")
      (value "Res3")
      (footprint "6-0805_N")
      (description "Resistor")
      (fields (field (name "ALTIUM_VALUE") "0R") (field (name "PUBLISHER") "Altium Limited"))
      (libsource (lib "Miscellaneous Devices") (part "Res3"))
    )
    (comp (ref "R57")
      (value "Res3")
      (footprint "6-0805_N")
      (description "Resistor")
      (fields (field (name "ALTIUM_VALUE") "10k") (field (name "PUBLISHER") "Altium Limited"))
      (libsource (lib "Miscellaneous Devices") (part "Res3"))
    )
    (comp (ref "R58")
      (value "Res3")
      (footprint "6-0805_N")
      (description "Resistor")
      (fields (field (name "ALTIUM_VALUE") "470R") (field (name "PUBLISHER") "Altium Limited"))
      (libsource (lib "Miscellaneous Devices") (part "Res3"))
    )
    (comp (ref "R59")
      (value "Res3")
      (footprint "6-0805_N")
      (description "Resistor")
      (fields (field (name "ALTIUM_VALUE") "1kR") (field (name "PUBLISHER") "Altium Limited"))
      (libsource (lib "Miscellaneous Devices") (part "Res3"))
    )
    (comp (ref "R60")
      (value "Res_Pack_100R")
      (footprint "Res_Pack_0603")
      (description "Res_Pack_4")
      (libsource (lib "Simon'Library") (part "Res_Pack_4"))
    )
    (comp (ref "R61")
      (value "Res_Pack_100R")
      (footprint "Res_Pack_0603")
      (description "Res_Pack_4")
      (libsource (lib "Simon'Library") (part "Res_Pack_4"))
    )
    (comp (ref "R62")
      (value "Res3")
      (footprint "6-0805_N")
      (description "Resistor")
      (fields (field (name "ALTIUM_VALUE") "1K") (field (name "PUBLISHER") "Altium Limited"))
      (libsource (lib "Miscellaneous Devices") (part "Res3"))
    )
    (comp (ref "R63")
      (value "Res3")
      (footprint "6-0805_N")
      (description "Resistor")
      (fields (field (name "ALTIUM_VALUE") "1k") (field (name "PUBLISHER") "Altium Limited"))
      (libsource (lib "Miscellaneous Devices") (part "Res3"))
    )
    (comp (ref "R64")
      (value "Res3")
      (footprint "6-0805_N")
      (description "Resistor")
      (fields (field (name "ALTIUM_VALUE") "0R") (field (name "PUBLISHER") "Altium Limited"))
      (libsource (lib "Miscellaneous Devices") (part "Res3"))
    )
    (comp (ref "S1")
      (value "SW DIP-8")
      (footprint "DHN(F)_8Pin")
      (description "DIP Switch, 8 Position, SPST")
      (fields (field (name "PUBLISHER") "Altium Limited"))
      (libsource (lib "Miscellaneous Devices") (part "SW DIP-8"))
    )
    (comp (ref "S2")
      (value "Reset")
      (footprint "SWP_PB_6.5mm")
      (description "Switch")
      (fields (field (name "PUBLISHER") "Altium Limited"))
      (libsource (lib "Miscellaneous Devices") (part "SW-PB"))
    )
    (comp (ref "U1") (value "MQ_Alcohol") (footprint "MQ") (libsource (lib "Simon'Library") (part "MQ")))
    (comp (ref "U2")
      (value "M62429")
      (footprint "SO8_N")
      (description "Digital Adjust Res")
      (libsource (lib "Simon'Library") (part "M62429"))
    )
    (comp (ref "U3")
      (value "LM2576SX-5.0")
      (footprint "TS5B_L")
      (description "SIMPLE SWITCHER® 3A Step-Down Voltage Regulator, 5-pin TO-263")
      (fields (field (name "MANUFACTURER") "National Semiconductor"))
      (libsource (lib "Altium Content Vault") (part "PM-REG-LM2575HVS-12"))
    )
    (comp (ref "U4")
      (value "AMS1117")
      (footprint "SOT223_N")
      (libsource (lib "Simon'Library") (part "AMS1117"))
    )
    (comp (ref "U5")
      (value "ESP-07")
      (footprint "ESP-07_Wifi")
      (libsource (lib "Simon'Library") (part "ESP-07_Wifi"))
    )
    (comp (ref "U6")
      (value "LM2904M")
      (footprint "D0008A_M")
      (description "Low Power Dual Operational Amplifier, 8-pin Narrow SOIC")
      (fields (field (name "MANUFACTURER") "Texas Instruments"))
      (libsource (lib "Altium Content Vault") (part "AMP-OPA-LM158-8"))
    )
    (comp (ref "U7")
      (value "DS18B20")
      (footprint "TO-92A")
      (libsource (lib "Simon'Library") (part "DS18B20"))
    )
    (comp (ref "U8")
      (value "MMA8452Q")
      (footprint "QFN-16")
      (libsource (lib "Simon'Library") (part "MMA8452Q"))
    )
    (comp (ref "U9")
      (value "LM2904M")
      (footprint "D0008A_M")
      (description "Low Power Dual Operational Amplifier, 8-pin Narrow SOIC")
      (fields (field (name "MANUFACTURER") "Texas Instruments"))
      (libsource (lib "Altium Content Vault") (part "AMP-OPA-LM158-8"))
    )
    (comp (ref "U10")
      (value "STM32F103RCT6")
      (footprint "LQFP64_L")
      (libsource (lib "Altium Content Vault") (part "MC-ARM-STM32F101-SQ64"))
    )
    (comp (ref "U11")
      (value "LM358AMX")
      (footprint "M08A_M")
      (description "Low Power Dual Operational Amplifier, 8-pin Narrow SOIC")
      (fields (field (name "MANUFACTURER") "National Semiconductor"))
      (libsource (lib "Altium Content Vault") (part "AMP-OPA-LM158-8"))
    )
    (comp (ref "U12")
      (value "LM2904M")
      (footprint "D0008A_M")
      (description "Low Power Dual Operational Amplifier, 8-pin Narrow SOIC")
      (fields (field (name "MANUFACTURER") "Texas Instruments"))
      (libsource (lib "Altium Content Vault") (part "AMP-OPA-LM158-8"))
    )
    (comp (ref "U13")
      (value "KP10104CTLD")
      (footprint "KP10104CTLD")
      (description "4-Pin Phototransistor Optocoupler")
      (fields (field (name "PUBLISHER") "Altium Limited"))
      (libsource (lib "Miscellaneous Devices") (part "Optoisolator1"))
    )
    (comp (ref "U14")
      (value "KP10104CTLD")
      (footprint "KP10104CTLD")
      (description "4-Pin Phototransistor Optocoupler")
      (fields (field (name "PUBLISHER") "Altium Limited"))
      (libsource (lib "Miscellaneous Devices") (part "Optoisolator1"))
    )
    (comp (ref "U15")
      (value "KP10104CTLD")
      (footprint "KP10104CTLD")
      (description "4-Pin Phototransistor Optocoupler")
      (fields (field (name "PUBLISHER") "Altium Limited"))
      (libsource (lib "Miscellaneous Devices") (part "Optoisolator1"))
    )
    (comp (ref "U16")
      (value "KP10104CTLD")
      (footprint "KP10104CTLD")
      (description "4-Pin Phototransistor Optocoupler")
      (fields (field (name "PUBLISHER") "Altium Limited"))
      (libsource (lib "Miscellaneous Devices") (part "Optoisolator1"))
    )
    (comp (ref "U17")
      (value "CS8508E")
      (footprint "SO8_L")
      (description "Audio Amplifier")
      (libsource (lib "Simon'Library") (part "CS8508E"))
    )
    (comp (ref "Y1")
      (value "XTAL")
      (footprint "OSC_5032_2Pin")
      (description "Crystal Oscillator")
      (fields (field (name "PUBLISHER") "Altium Limited"))
      (libsource (lib "Miscellaneous Devices") (part "XTAL"))
    )
  )
  (nets
    (net (code "1") (name "+3.3V") (class "Default")
      (node (ref "C10") (pin "1") (pinfunction "1_1") (pintype "passive"))
      (node (ref "C11") (pin "1") (pinfunction "1_1") (pintype "passive"))
      (node (ref "C13") (pin "1") (pinfunction "1_1") (pintype "passive"))
      (node (ref "C14") (pin "1") (pinfunction "1_1") (pintype "passive"))
      (node (ref "C18") (pin "2") (pinfunction "2_2") (pintype "passive"))
      (node (ref "C19") (pin "2") (pinfunction "2_2") (pintype "passive"))
      (node (ref "C27") (pin "2") (pinfunction "2_2") (pintype "passive"))
      (node (ref "C28") (pin "2") (pinfunction "2_2") (pintype "passive"))
      (node (ref "C37") (pin "1") (pinfunction "1_1") (pintype "passive"))
      (node (ref "C38") (pin "1") (pinfunction "1_1") (pintype "passive"))
      (node (ref "C43") (pin "1") (pinfunction "1_1") (pintype "passive"))
      (node (ref "C44") (pin "1") (pinfunction "1_1") (pintype "passive"))
      (node (ref "P12") (pin "1") (pinfunction "1_1") (pintype "passive"))
      (node (ref "R11") (pin "2") (pinfunction "2_2") (pintype "passive"))
      (node (ref "R15") (pin "2") (pinfunction "2_2") (pintype "passive"))
      (node (ref "R19") (pin "2") (pinfunction "2_2") (pintype "passive"))
      (node (ref "R24") (pin "2") (pinfunction "2_2") (pintype "passive"))
      (node (ref "R25") (pin "2") (pinfunction "2_2") (pintype "passive"))
      (node (ref "R29") (pin "2") (pinfunction "2_2") (pintype "passive"))
      (node (ref "R30") (pin "2") (pinfunction "2_2") (pintype "passive"))
      (node (ref "R34") (pin "2") (pinfunction "2_2") (pintype "passive"))
      (node (ref "R35") (pin "2") (pinfunction "2_2") (pintype "passive"))
      (node (ref "R38") (pin "2") (pinfunction "2_2") (pintype "passive"))
      (node (ref "R39") (pin "2") (pinfunction "2_2") (pintype "passive"))
      (node (ref "R48") (pin "8") (pinfunction "VCC_8") (pintype "passive"))
      (node (ref "R57") (pin "1") (pinfunction "1_1") (pintype "passive"))
      (node (ref "R6") (pin "2") (pinfunction "2_2") (pintype "passive"))
      (node (ref "R64") (pin "1") (pinfunction "1_1") (pintype "passive"))
      (node (ref "U10") (pin "13") (pinfunction "VDDA_13") (pintype "power_in"))
      (node (ref "U10") (pin "19") (pinfunction "VDD_4_19") (pintype "power_in"))
      (node (ref "U10") (pin "32") (pinfunction "VDD_1_32") (pintype "power_in"))
      (node (ref "U10") (pin "48") (pinfunction "VDD_2_48") (pintype "power_in"))
      (node (ref "U10") (pin "64") (pinfunction "VDD_3_64") (pintype "power_in"))
      (node (ref "U4") (pin "4") (pinfunction "Vout_4") (pintype "passive"))
      (node (ref "U5") (pin "1") (pinfunction "RST_1") (pintype "passive"))
      (node (ref "U5") (pin "8") (pinfunction "VCC_8") (pintype "passive"))
      (node (ref "U7") (pin "3") (pinfunction "VDD_3") (pintype "passive"))
      (node (ref "U8") (pin "1") (pinfunction "VDDIO_1") (pintype "passive"))
      (node (ref "U8") (pin "14") (pinfunction "VDD_14") (pintype "passive"))
    )
    (net (code "2") (name "+5V") (class "Default")
      (node (ref "C3") (pin "2") (pinfunction "2_2") (pintype "passive"))
      (node (ref "C45") (pin "1") (pinfunction "1_1") (pintype "passive"))
      (node (ref "C46") (pin "1") (pinfunction "1_1") (pintype "passive"))
      (node (ref "C47") (pin "1") (pinfunction "1_1") (pintype "passive"))
      (node (ref "C49") (pin "1") (pinfunction "1_1") (pintype "passive"))
      (node (ref "C50") (pin "1") (pinfunction "1_1") (pintype "passive"))
      (node (ref "C6") (pin "1") (pinfunction "1_1") (pintype "passive"))
      (node (ref "D12") (pin "2") (pinfunction "K_2") (pintype "passive"))
      (node (ref "D14") (pin "2") (pinfunction "K_2") (pintype "passive"))
      (node (ref "D16") (pin "2") (pinfunction "K_2") (pintype "passive"))
      (node (ref "D6") (pin "2") (pinfunction "K_2") (pintype "passive"))
      (node (ref "D8") (pin "2") (pinfunction "K_2") (pintype "passive"))
      (node (ref "D9") (pin "2") (pinfunction "K_2") (pintype "passive"))
      (node (ref "L2") (pin "2") (pinfunction "2_2") (pintype "passive"))
      (node (ref "L3") (pin "2") (pinfunction "2_2") (pintype "passive"))
      (node (ref "LS1") (pin "1") (pinfunction "1_1") (pintype "passive"))
      (node (ref "P13") (pin "1") (pinfunction "1_1") (pintype "passive"))
      (node (ref "P7") (pin "1") (pinfunction "1_1") (pintype "passive"))
      (node (ref "P8") (pin "10") (pinfunction "VDD_10") (pintype "passive"))
      (node (ref "R1") (pin "1") (pinfunction "1_1") (pintype "passive"))
      (node (ref "R10") (pin "1") (pinfunction "1_1") (pintype "passive"))
      (node (ref "R13") (pin "1") (pinfunction "1_1") (pintype "passive"))
      (node (ref "R17") (pin "1") (pinfunction "1_1") (pintype "passive"))
      (node (ref "U1") (pin "1") (pinfunction "A_1") (pintype "passive"))
      (node (ref "U1") (pin "2") (pinfunction "H_2") (pintype "passive"))
      (node (ref "U11") (pin "8") (pinfunction "V+_8") (pintype "power_in"))
      (node (ref "U12") (pin "8") (pinfunction "V+_8") (pintype "power_in"))
      (node (ref "U16") (pin "1") (pinfunction "A_1") (pintype "passive"))
      (node (ref "U17") (pin "5") (pinfunction "VDD_5") (pintype "passive"))
      (node (ref "U4") (pin "3") (pinfunction "Vin_3") (pintype "passive"))
      (node (ref "U6") (pin "8") (pinfunction "V+_8") (pintype "power_in"))
      (node (ref "U9") (pin "8") (pinfunction "V+_8") (pintype "power_in"))
    )
    (net (code "3") (name "+12V") (class "Default")
      (node (ref "C12") (pin "1") (pinfunction "1_1") (pintype "passive"))
      (node (ref "C4") (pin "1") (pinfunction "1_1") (pintype "passive"))
      (node (ref "C5") (pin "1") (pinfunction "1_1") (pintype "passive"))
      (node (ref "C7") (pin "1") (pinfunction "1_1") (pintype "passive"))
      (node (ref "C9") (pin "1") (pinfunction "1_1") (pintype "passive"))
      (node (ref "CB1") (pin "2") (pinfunction "2_2") (pintype "passive"))
      (node (ref "D1") (pin "2") (pinfunction "K_2") (pintype "passive"))
      (node (ref "D3") (pin "2") (pinfunction "K_2") (pintype "passive"))
      (node (ref "D5") (pin "2") (pinfunction "K_2") (pintype "passive"))
      (node (ref "P2") (pin "1") (pinfunction "1_1") (pintype "passive"))
      (node (ref "P4") (pin "1") (pinfunction "1_1") (pintype "passive"))
      (node (ref "P6") (pin "1") (pinfunction "1_1") (pintype "passive"))
      (node (ref "P9") (pin "1") (pinfunction "1_1") (pintype "passive"))
      (node (ref "R4") (pin "2") (pinfunction "2_2") (pintype "passive"))
      (node (ref "U3") (pin "1") (pinfunction "VIN_1") (pintype "power_in"))
    )
    (net (code "4") (name "/ADS_IN") (class "Default")
      (node (ref "C26") (pin "2") (pinfunction "2_2") (pintype "passive"))
      (node (ref "D11") (pin "2") (pinfunction "K_2") (pintype "passive"))
      (node (ref "D9") (pin "1") (pinfunction "A_1") (pintype "passive"))
      (node (ref "R32") (pin "1") (pinfunction "1_1") (pintype "passive"))
      (node (ref "U10") (pin "50") (pinfunction "PA15_50") (pintype "bidirectional"))
    )
    (net (code "5") (name "/ADS_OUT") (class "Default")
      (node (ref "C24") (pin "2") (pinfunction "2_2") (pintype "passive"))
      (node (ref "P5") (pin "1") (pinfunction "1_1") (pintype "passive"))
      (node (ref "R36") (pin "2") (pinfunction "2_2") (pintype "passive"))
      (node (ref "R64") (pin "2") (pinfunction "2_2") (pintype "passive"))
    )
    (net (code "6") (name "/AD_IN") (class "Default")
      (node (ref "C17") (pin "2") (pinfunction "2_2") (pintype "passive"))
      (node (ref "D6") (pin "1") (pinfunction "A_1") (pintype "passive"))
      (node (ref "D7") (pin "2") (pinfunction "K_2") (pintype "passive"))
      (node (ref "R26") (pin "1") (pinfunction "1_1") (pintype "passive"))
      (node (ref "U10") (pin "17") (pinfunction "PA3_17") (pintype "bidirectional"))
    )
    (net (code "7") (name "/AD_OUT") (class "Default")
      (node (ref "C15") (pin "2") (pinfunction "2_2") (pintype "passive"))
      (node (ref "P5") (pin "2") (pinfunction "2_2") (pintype "passive"))
      (node (ref "R27") (pin "2") (pinfunction "2_2") (pintype "passive"))
    )
    (net (code "8") (name "/AUDIO") (class "Default")
      (node (ref "C1") (pin "1") (pinfunction "1_1") (pintype "passive"))
      (node (ref "U10") (pin "20") (pinfunction "PA4_20") (pintype "bidirectional"))
    )
    (net (code "9") (name "/Alcohol_C") (class "Default")
      (node (ref "R5") (pin "1") (pinfunction "1_1") (pintype "passive"))
      (node (ref "U1") (pin "6") (pinfunction "B_6") (pintype "passive"))
      (node (ref "U10") (pin "24") (pinfunction "PC4_24") (pintype "bidirectional"))
    )
    (net (code "10") (name "/Bee") (class "Default")
      (node (ref "R14") (pin "2") (pinfunction "2_2") (pintype "passive"))
      (node (ref "U10") (pin "38") (pinfunction "PC7_38") (pintype "bidirectional"))
    )
    (net (code "11") (name "/CS_SD") (class "Default")
      (node (ref "R2") (pin "1") (pinfunction "1_1") (pintype "passive"))
      (node (ref "U10") (pin "55") (pinfunction "PB3_55") (pintype "bidirectional"))
    )
    (net (code "12") (name "/Debug_Rx") (class "Default")
      (node (ref "R63") (pin "2") (pinfunction "2_2") (pintype "passive"))
      (node (ref "U10") (pin "43") (pinfunction "PA10_43") (pintype "bidirectional"))
    )
    (net (code "13") (name "/Debug_Tx") (class "Default")
      (node (ref "R56") (pin "2") (pinfunction "2_2") (pintype "passive"))
      (node (ref "U10") (pin "42") (pinfunction "PA9_42") (pintype "bidirectional"))
    )
    (net (code "14") (name "/E2_SCL") (class "Default")
      (node (ref "R48") (pin "6") (pinfunction "SCL_6") (pintype "passive"))
      (node (ref "U10") (pin "25") (pinfunction "PC5_25") (pintype "bidirectional"))
    )
    (net (code "15") (name "/E2_SDA") (class "Default")
      (node (ref "R48") (pin "5") (pinfunction "SDA_5") (pintype "passive"))
      (node (ref "U10") (pin "26") (pinfunction "PB0_26") (pintype "bidirectional"))
    )
    (net (code "16") (name "/FHD_IN") (class "Default")
      (node (ref "C31") (pin "2") (pinfunction "2_2") (pintype "passive"))
      (node (ref "D12") (pin "1") (pinfunction "A_1") (pintype "passive"))
      (node (ref "D13") (pin "2") (pinfunction "K_2") (pintype "passive"))
      (node (ref "R40") (pin "1") (pinfunction "1_1") (pintype "passive"))
      (node (ref "U10") (pin "14") (pinfunction "PA0-WKUP_14") (pintype "bidirectional"))
    )
    (net (code "17") (name "/FHD_OUT") (class "Default")
      (node (ref "C19") (pin "1") (pinfunction "1_1") (pintype "passive"))
      (node (ref "C29") (pin "2") (pinfunction "2_2") (pintype "passive"))
      (node (ref "P10") (pin "1") (pinfunction "1_1") (pintype "passive"))
      (node (ref "R35") (pin "1") (pinfunction "1_1") (pintype "passive"))
      (node (ref "R41") (pin "2") (pinfunction "2_2") (pintype "passive"))
    )
    (net (code "18") (name "/FLD_IN") (class "Default")
      (node (ref "C23") (pin "2") (pinfunction "2_2") (pintype "passive"))
      (node (ref "D10") (pin "2") (pinfunction "K_2") (pintype "passive"))
      (node (ref "D8") (pin "1") (pinfunction "A_1") (pintype "passive"))
      (node (ref "R31") (pin "1") (pinfunction "1_1") (pintype "passive"))
      (node (ref "U10") (pin "11") (pinfunction "PC3_11") (pintype "bidirectional"))
    )
    (net (code "19") (name "/FLD_OUT") (class "Default")
      (node (ref "C18") (pin "1") (pinfunction "1_1") (pintype "passive"))
      (node (ref "C21") (pin "2") (pinfunction "2_2") (pintype "passive"))
      (node (ref "P10") (pin "2") (pinfunction "2_2") (pintype "passive"))
      (node (ref "R33") (pin "2") (pinfunction "2_2") (pintype "passive"))
      (node (ref "R34") (pin "1") (pinfunction "1_1") (pintype "passive"))
    )
    (net (code "20") (name "/Fan") (class "Default")
      (node (ref "R15") (pin "1") (pinfunction "1_1") (pintype "passive"))
      (node (ref "R16") (pin "1") (pinfunction "1_1") (pintype "passive"))
      (node (ref "R43") (pin "2") (pinfunction "2_2") (pintype "passive"))
      (node (ref "U10") (pin "28") (pinfunction "PB2_28") (pintype "bidirectional"))
    )
    (net (code "21") (name "/Fire_Tem_D") (class "Default")
      (node (ref "R42") (pin "2") (pinfunction "2_2") (pintype "passive"))
      (node (ref "U10") (pin "8") (pinfunction "PC0_8") (pintype "bidirectional"))
      (node (ref "U11") (pin "1") (pinfunction "OUTA_1") (pintype "output"))
    )
    (net (code "22") (name "/Fire_Tem_T") (class "Default")
      (node (ref "R51") (pin "2") (pinfunction "2_2") (pintype "passive"))
      (node (ref "U10") (pin "9") (pinfunction "PC1_9") (pintype "bidirectional"))
      (node (ref "U11") (pin "7") (pinfunction "OUTB_7") (pintype "output"))
    )
    (net (code "23") (name "/Fire_UP") (class "Default")
      (node (ref "R11") (pin "1") (pinfunction "1_1") (pintype "passive"))
      (node (ref "R12") (pin "1") (pinfunction "1_1") (pintype "passive"))
      (node (ref "U10") (pin "10") (pinfunction "PC2_10") (pintype "bidirectional"))
    )
    (net (code "24") (name "/IO1") (class "Default")
      (node (ref "R61") (pin "1") (pinfunction "1_1") (pintype "passive"))
      (node (ref "U10") (pin "58") (pinfunction "PB6_58") (pintype "bidirectional"))
    )
    (net (code "25") (name "/IO2") (class "Default")
      (node (ref "R61") (pin "2") (pinfunction "2_2") (pintype "passive"))
      (node (ref "U10") (pin "59") (pinfunction "PB7_59") (pintype "bidirectional"))
    )
    (net (code "26") (name "/IO3") (class "Default")
      (node (ref "R61") (pin "3") (pinfunction "3_3") (pintype "passive"))
      (node (ref "U10") (pin "61") (pinfunction "PB8_61") (pintype "bidirectional"))
    )
    (net (code "27") (name "/IO4") (class "Default")
      (node (ref "R61") (pin "4") (pinfunction "4_4") (pintype "passive"))
      (node (ref "U10") (pin "62") (pinfunction "PB9_62") (pintype "bidirectional"))
    )
    (net (code "28") (name "/LDHD_IN") (class "Default")
      (node (ref "C42") (pin "2") (pinfunction "2_2") (pintype "passive"))
      (node (ref "D16") (pin "1") (pinfunction "A_1") (pintype "passive"))
      (node (ref "D17") (pin "2") (pinfunction "K_2") (pintype "passive"))
      (node (ref "R58") (pin "1") (pinfunction "1_1") (pintype "passive"))
      (node (ref "U10") (pin "23") (pinfunction "PA7_23") (pintype "bidirectional"))
    )
    (net (code "29") (name "/LDHD_OUT") (class "Default")
      (node (ref "C28") (pin "1") (pinfunction "1_1") (pintype "passive"))
      (node (ref "C40") (pin "2") (pinfunction "2_2") (pintype "passive"))
      (node (ref "P11") (pin "1") (pinfunction "1_1") (pintype "passive"))
      (node (ref "R39") (pin "1") (pinfunction "1_1") (pintype "passive"))
      (node (ref "R59") (pin "2") (pinfunction "2_2") (pintype "passive"))
    )
    (net (code "30") (name "/LDLD_IN") (class "Default")
      (node (ref "C36") (pin "2") (pinfunction "2_2") (pintype "passive"))
      (node (ref "D14") (pin "1") (pinfunction "A_1") (pintype "passive"))
      (node (ref "D15") (pin "2") (pinfunction "K_2") (pintype "passive"))
      (node (ref "R49") (pin "1") (pinfunction "1_1") (pintype "passive"))
      (node (ref "U10") (pin "22") (pinfunction "PA6_22") (pintype "bidirectional"))
    )
    (net (code "31") (name "/LDLD_OUT") (class "Default")
      (node (ref "C27") (pin "1") (pinfunction "1_1") (pintype "passive"))
      (node (ref "C34") (pin "2") (pinfunction "2_2") (pintype "passive"))
      (node (ref "P11") (pin "2") (pinfunction "2_2") (pintype "passive"))
      (node (ref "R38") (pin "1") (pinfunction "1_1") (pintype "passive"))
      (node (ref "R50") (pin "2") (pinfunction "2_2") (pintype "passive"))
    )
    (net (code "32") (name "/M6_CLK") (class "Default")
      (node (ref "U10") (pin "41") (pinfunction "PA8_41") (pintype "bidirectional"))
      (node (ref "U2") (pin "5") (pinfunction "CLK_5") (pintype "passive"))
    )
    (net (code "33") (name "/M6_Data") (class "Default")
      (node (ref "U10") (pin "21") (pinfunction "PA5_21") (pintype "bidirectional"))
      (node (ref "U2") (pin "4") (pinfunction "DATA_4") (pintype "passive"))
    )
    (net (code "34") (name "/MMA_SCL") (class "Default")
      (node (ref "R29") (pin "1") (pinfunction "1_1") (pintype "passive"))
      (node (ref "U10") (pin "57") (pinfunction "PB5_57") (pintype "bidirectional"))
      (node (ref "U8") (pin "4") (pinfunction "SCL_4") (pintype "passive"))
    )
    (net (code "35") (name "/MMA_SDA") (class "Default")
      (node (ref "R30") (pin "1") (pinfunction "1_1") (pintype "passive"))
      (node (ref "U10") (pin "56") (pinfunction "PB4_56") (pintype "bidirectional"))
      (node (ref "U8") (pin "6") (pinfunction "SDA_6") (pintype "passive"))
    )
    (net (code "36") (name "/Pump1") (class "Default")
      (node (ref "R19") (pin "1") (pinfunction "1_1") (pintype "passive"))
      (node (ref "R22") (pin "1") (pinfunction "1_1") (pintype "passive"))
      (node (ref "U10") (pin "15") (pinfunction "PA1_15") (pintype "bidirectional"))
    )
    (net (code "37") (name "/Pump2") (class "Default")
      (node (ref "R6") (pin "1") (pinfunction "1_1") (pintype "passive"))
      (node (ref "R7") (pin "1") (pinfunction "1_1") (pintype "passive"))
      (node (ref "U10") (pin "16") (pinfunction "PA2_16") (pintype "bidirectional"))
    )
    (net (code "38") (name "/SR_D0") (class "Default")
      (node (ref "R20") (pin "2") (pinfunction "2_2") (pintype "passive"))
      (node (ref "U10") (pin "35") (pinfunction "PB14_35") (pintype "bidirectional"))
    )
    (net (code "39") (name "/SR_D1") (class "Default")
      (node (ref "R21") (pin "2") (pinfunction "2_2") (pintype "passive"))
      (node (ref "U10") (pin "36") (pinfunction "PB15_36") (pintype "bidirectional"))
    )
    (net (code "40") (name "/SR_D2") (class "Default")
      (node (ref "R23") (pin "2") (pinfunction "2_2") (pintype "passive"))
      (node (ref "U10") (pin "37") (pinfunction "PC6_37") (pintype "bidirectional"))
    )
    (net (code "41") (name "/SR_LED") (class "Default")
      (node (ref "R62") (pin "2") (pinfunction "2_2") (pintype "passive"))
      (node (ref "U10") (pin "33") (pinfunction "PB12_33") (pintype "bidirectional"))
    )
    (net (code "42") (name "/SR_SW") (class "Default")
      (node (ref "R18") (pin "2") (pinfunction "2_2") (pintype "passive"))
      (node (ref "U10") (pin "34") (pinfunction "PB13_34") (pintype "bidirectional"))
    )
    (net (code "43") (name "/SW1") (class "Default")
      (node (ref "S1") (pin "1") (pinfunction "A1_1") (pintype "passive"))
      (node (ref "U10") (pin "51") (pinfunction "PC10_51") (pintype "bidirectional"))
    )
    (net (code "44") (name "/SW2") (class "Default")
      (node (ref "S1") (pin "2") (pinfunction "A2_2") (pintype "passive"))
      (node (ref "U10") (pin "52") (pinfunction "PC11_52") (pintype "bidirectional"))
    )
    (net (code "45") (name "/SW3") (class "Default")
      (node (ref "S1") (pin "3") (pinfunction "A3_3") (pintype "passive"))
      (node (ref "U10") (pin "53") (pinfunction "PC12_53") (pintype "bidirectional"))
    )
    (net (code "46") (name "/SW4") (class "Default")
      (node (ref "S1") (pin "4") (pinfunction "A4_4") (pintype "passive"))
      (node (ref "U10") (pin "54") (pinfunction "PD2_54") (pintype "bidirectional"))
    )
    (net (code "47") (name "/SW5") (class "Default")
      (node (ref "S1") (pin "5") (pinfunction "A5_5") (pintype "passive"))
      (node (ref "U10") (pin "45") (pinfunction "PA12_45") (pintype "bidirectional"))
    )
    (net (code "48") (name "/SW6") (class "Default")
      (node (ref "S1") (pin "6") (pinfunction "A6_6") (pintype "passive"))
      (node (ref "U10") (pin "44") (pinfunction "PA11_44") (pintype "bidirectional"))
    )
    (net (code "49") (name "/SW7") (class "Default")
      (node (ref "S1") (pin "7") (pinfunction "A7_7") (pintype "passive"))
      (node (ref "U10") (pin "40") (pinfunction "PC9_40") (pintype "bidirectional"))
    )
    (net (code "50") (name "/SW8") (class "Default")
      (node (ref "S1") (pin "8") (pinfunction "A8_8") (pintype "passive"))
      (node (ref "U10") (pin "39") (pinfunction "PC8_39") (pintype "bidirectional"))
    )
    (net (code "51") (name "/SWCLK") (class "Default")
      (node (ref "R55") (pin "2") (pinfunction "2_2") (pintype "passive"))
      (node (ref "U10") (pin "49") (pinfunction "PA14_49") (pintype "bidirectional"))
    )
    (net (code "52") (name "/SWDIO") (class "Default")
      (node (ref "R47") (pin "2") (pinfunction "2_2") (pintype "passive"))
      (node (ref "U10") (pin "46") (pinfunction "PA13_46") (pintype "bidirectional"))
    )
    (net (code "53") (name "/Tem") (class "Default")
      (node (ref "R25") (pin "1") (pinfunction "1_1") (pintype "passive"))
      (node (ref "U10") (pin "27") (pinfunction "PB1_27") (pintype "bidirectional"))
      (node (ref "U7") (pin "2") (pinfunction "DQ_2") (pintype "passive"))
    )
    (net (code "54") (name "/WIFI_RX") (class "Default")
      (node (ref "U10") (pin "29") (pinfunction "PB10_29") (pintype "bidirectional"))
      (node (ref "U5") (pin "15") (pinfunction "RXD0_15") (pintype "passive"))
    )
    (net (code "55") (name "/WIFI_TX") (class "Default")
      (node (ref "U10") (pin "30") (pinfunction "PB11_30") (pintype "bidirectional"))
      (node (ref "U5") (pin "16") (pinfunction "TXD0_16") (pintype "passive"))
    )
    (net (code "56") (name "Net-(C2-Pad1)") (class "Default")
      (node (ref "C2") (pin "1") (pinfunction "1_1") (pintype "passive"))
      (node (ref "R46") (pin "1") (pinfunction "1_1") (pintype "passive"))
    )
    (net (code "57") (name "Net-(CB1-Pad1)") (class "Default")
      (node (ref "CB1") (pin "1") (pinfunction "1_1") (pintype "passive"))
      (node (ref "P1") (pin "1") (pinfunction "1_1") (pintype "passive"))
    )
    (net (code "58") (name "Net-(D1-A)") (class "Default")
      (node (ref "C4") (pin "2") (pinfunction "2_2") (pintype "passive"))
      (node (ref "C5") (pin "2") (pinfunction "2_2") (pintype "passive"))
      (node (ref "D1") (pin "1") (pinfunction "A_1") (pintype "passive"))
      (node (ref "P2") (pin "2") (pinfunction "2_2") (pintype "passive"))
      (node (ref "Q1") (pin "2") (pinfunction "D_2") (pintype "passive"))
    )
    (net (code "59") (name "Net-(D2-A)") (class "Default")
      (node (ref "D2") (pin "1") (pinfunction "A_1") (pintype "passive"))
      (node (ref "R4") (pin "1") (pinfunction "1_1") (pintype "passive"))
    )
    (net (code "60") (name "Net-(D3-A)") (class "Default")
      (node (ref "C9") (pin "2") (pinfunction "2_2") (pintype "passive"))
      (node (ref "D3") (pin "1") (pinfunction "A_1") (pintype "passive"))
      (node (ref "P6") (pin "2") (pinfunction "2_2") (pintype "passive"))
      (node (ref "Q6") (pin "2") (pinfunction "D_2") (pintype "passive"))
    )
    (net (code "61") (name "Net-(D4-K)") (class "Default")
      (node (ref "D4") (pin "2") (pinfunction "K_2") (pintype "passive"))
      (node (ref "L1") (pin "1") (pinfunction "1_1") (pintype "passive"))
      (node (ref "U3") (pin "2") (pinfunction "OUT_2") (pintype "power_in"))
    )
    (net (code "62") (name "Net-(D5-A)") (class "Default")
      (node (ref "C12") (pin "2") (pinfunction "2_2") (pintype "passive"))
      (node (ref "D5") (pin "1") (pinfunction "A_1") (pintype "passive"))
      (node (ref "P9") (pin "2") (pinfunction "2_2") (pintype "passive"))
      (node (ref "Q8") (pin "2") (pinfunction "D_2") (pintype "passive"))
    )
    (net (code "63") (name "Net-(P7-Pad2)") (class "Default")
      (node (ref "P7") (pin "2") (pinfunction "2_2") (pintype "passive"))
      (node (ref "R60") (pin "8") (pinfunction "8_8") (pintype "passive"))
    )
    (net (code "64") (name "Net-(P7-Pad3)") (class "Default")
      (node (ref "P7") (pin "3") (pinfunction "3_3") (pintype "passive"))
      (node (ref "R60") (pin "7") (pinfunction "7_7") (pintype "passive"))
    )
    (net (code "65") (name "Net-(P7-Pad4)") (class "Default")
      (node (ref "P7") (pin "4") (pinfunction "4_4") (pintype "passive"))
      (node (ref "R60") (pin "6") (pinfunction "6_6") (pintype "passive"))
    )
    (net (code "66") (name "Net-(P7-Pad5)") (class "Default")
      (node (ref "P7") (pin "5") (pinfunction "5_5") (pintype "passive"))
      (node (ref "R60") (pin "5") (pinfunction "5_5") (pintype "passive"))
    )
    (net (code "67") (name "Net-(P8-D0)") (class "Default")
      (node (ref "P8") (pin "6") (pinfunction "D0_6") (pintype "passive"))
      (node (ref "R20") (pin "1") (pinfunction "1_1") (pintype "passive"))
    )
    (net (code "68") (name "Net-(P8-D1)") (class "Default")
      (node (ref "P8") (pin "7") (pinfunction "D1_7") (pintype "passive"))
      (node (ref "R21") (pin "1") (pinfunction "1_1") (pintype "passive"))
    )
    (net (code "69") (name "Net-(P8-D2)") (class "Default")
      (node (ref "P8") (pin "8") (pinfunction "D2_8") (pintype "passive"))
      (node (ref "R23") (pin "1") (pinfunction "1_1") (pintype "passive"))
    )
    (net (code "70") (name "Net-(P8-LED)") (class "Default")
      (node (ref "P8") (pin "3") (pinfunction "LED_3") (pintype "passive"))
      (node (ref "R62") (pin "1") (pinfunction "1_1") (pintype "passive"))
    )
    (net (code "71") (name "Net-(P8-SW)") (class "Default")
      (node (ref "P8") (pin "4") (pinfunction "SW_4") (pintype "passive"))
      (node (ref "R18") (pin "1") (pinfunction "1_1") (pintype "passive"))
    )
    (net (code "72") (name "Net-(P12-Pad2)") (class "Default")
      (node (ref "P12") (pin "2") (pinfunction "2_2") (pintype "passive"))
      (node (ref "R47") (pin "1") (pinfunction "1_1") (pintype "passive"))
    )
    (net (code "73") (name "Net-(P12-Pad3)") (class "Default")
      (node (ref "P12") (pin "3") (pinfunction "3_3") (pintype "passive"))
      (node (ref "R55") (pin "1") (pinfunction "1_1") (pintype "passive"))
    )
    (net (code "74") (name "Net-(P13-Pad2)") (class "Default")
      (node (ref "P13") (pin "2") (pinfunction "2_2") (pintype "passive"))
      (node (ref "R56") (pin "1") (pinfunction "1_1") (pintype "passive"))
    )
    (net (code "75") (name "Net-(P13-Pad3)") (class "Default")
      (node (ref "P13") (pin "3") (pinfunction "3_3") (pintype "passive"))
      (node (ref "R63") (pin "1") (pinfunction "1_1") (pintype "passive"))
    )
    (net (code "76") (name "Net-(P14-Pad1)") (class "Default")
      (node (ref "P14") (pin "1") (pinfunction "1_1") (pintype "passive"))
      (node (ref "R44") (pin "1") (pinfunction "1_1") (pintype "passive"))
    )
    (net (code "77") (name "Net-(P15-Pad1)") (class "Default")
      (node (ref "P15") (pin "1") (pinfunction "1_1") (pintype "passive"))
      (node (ref "R52") (pin "1") (pinfunction "1_1") (pintype "passive"))
    )
    (net (code "78") (name "Net-(Q1-G)") (class "Default")
      (node (ref "Q1") (pin "1") (pinfunction "G_1") (pintype "passive"))
      (node (ref "Q2") (pin "3") (pinfunction "C_3") (pintype "passive"))
      (node (ref "R1") (pin "2") (pinfunction "2_2") (pintype "passive"))
    )
    (net (code "79") (name "Net-(Q2-B)") (class "Default")
      (node (ref "Q2") (pin "1") (pinfunction "B_1") (pintype "passive"))
      (node (ref "R7") (pin "2") (pinfunction "2_2") (pintype "passive"))
    )
    (net (code "80") (name "Net-(Q3-D)") (class "Default")
      (node (ref "P4") (pin "2") (pinfunction "2_2") (pintype "passive"))
      (node (ref "Q3") (pin "2") (pinfunction "D_2") (pintype "passive"))
    )
    (net (code "81") (name "Net-(Q3-G)") (class "Default")
      (node (ref "Q3") (pin "1") (pinfunction "G_1") (pintype "passive"))
      (node (ref "Q4") (pin "3") (pinfunction "C_3") (pintype "passive"))
      (node (ref "R10") (pin "2") (pinfunction "2_2") (pintype "passive"))
    )
    (net (code "82") (name "Net-(Q4-B)") (class "Default")
      (node (ref "Q4") (pin "1") (pinfunction "B_1") (pintype "passive"))
      (node (ref "R12") (pin "2") (pinfunction "2_2") (pintype "passive"))
    )
    (net (code "83") (name "Net-(Q5-B)") (class "Default")
      (node (ref "Q5") (pin "1") (pinfunction "B_1") (pintype "passive"))
      (node (ref "R14") (pin "1") (pinfunction "1_1") (pintype "passive"))
    )
    (net (code "84") (name "Net-(Q5-C)") (class "Default")
      (node (ref "LS1") (pin "2") (pinfunction "2_2") (pintype "passive"))
      (node (ref "Q5") (pin "3") (pinfunction "C_3") (pintype "passive"))
    )
    (net (code "85") (name "Net-(Q6-G)") (class "Default")
      (node (ref "Q6") (pin "1") (pinfunction "G_1") (pintype "passive"))
      (node (ref "Q7") (pin "3") (pinfunction "C_3") (pintype "passive"))
      (node (ref "R13") (pin "2") (pinfunction "2_2") (pintype "passive"))
    )
    (net (code "86") (name "Net-(Q7-B)") (class "Default")
      (node (ref "Q7") (pin "1") (pinfunction "B_1") (pintype "passive"))
      (node (ref "R16") (pin "2") (pinfunction "2_2") (pintype "passive"))
    )
    (net (code "87") (name "Net-(Q8-G)") (class "Default")
      (node (ref "Q8") (pin "1") (pinfunction "G_1") (pintype "passive"))
      (node (ref "Q9") (pin "3") (pinfunction "C_3") (pintype "passive"))
      (node (ref "R17") (pin "2") (pinfunction "2_2") (pintype "passive"))
    )
    (net (code "88") (name "Net-(Q9-B)") (class "Default")
      (node (ref "Q9") (pin "1") (pinfunction "B_1") (pintype "passive"))
      (node (ref "R22") (pin "2") (pinfunction "2_2") (pintype "passive"))
    )
    (net (code "89") (name "Net-(U2-VCC)") (class "Default")
      (node (ref "L2") (pin "1") (pinfunction "1_1") (pintype "passive"))
      (node (ref "U2") (pin "6") (pinfunction "VCC_6") (pintype "passive"))
    )
    (net (code "90") (name "Net-(U2-VIN1)") (class "Default")
      (node (ref "C1") (pin "2") (pinfunction "2_2") (pintype "passive"))
      (node (ref "U2") (pin "1") (pinfunction "VIN1_1") (pintype "passive"))
    )
    (net (code "91") (name "Net-(U2-VOUT1)") (class "Default")
      (node (ref "C2") (pin "2") (pinfunction "2_2") (pintype "passive"))
      (node (ref "U2") (pin "2") (pinfunction "VOUT1_2") (pintype "passive"))
    )
    (net (code "92") (name "Net-(U3-FB)") (class "Default")
      (node (ref "C8") (pin "1") (pinfunction "1_1") (pintype "passive"))
      (node (ref "L1") (pin "2") (pinfunction "2_2") (pintype "passive"))
      (node (ref "L3") (pin "1") (pinfunction "1_1") (pintype "passive"))
      (node (ref "U3") (pin "4") (pinfunction "FB_4") (pintype "input"))
    )
    (net (code "93") (name "Net-(U5-CH_PD)") (class "Default")
      (node (ref "R24") (pin "1") (pinfunction "1_1") (pintype "passive"))
      (node (ref "U5") (pin "3") (pinfunction "CH_PD_3") (pintype "passive"))
    )
    (net (code "94") (name "Net-(U5-GPIO15)") (class "Default")
      (node (ref "R28") (pin "1") (pinfunction "1_1") (pintype "passive"))
      (node (ref "U5") (pin "10") (pinfunction "GPIO15_10") (pintype "passive"))
    )
    (net (code "95") (name "Net-(U6A-INA+)") (class "Default")
      (node (ref "C16") (pin "2") (pinfunction "2_2") (pintype "passive"))
      (node (ref "R27") (pin "1") (pinfunction "1_1") (pintype "passive"))
      (node (ref "U6") (pin "3") (pinfunction "INA+_3") (pintype "input"))
    )
    (net (code "96") (name "Net-(U6A-INA-)") (class "Default")
      (node (ref "R26") (pin "2") (pinfunction "2_2") (pintype "passive"))
      (node (ref "U6") (pin "1") (pinfunction "OUTA_1") (pintype "output"))
      (node (ref "U6") (pin "2") (pinfunction "INA-_2") (pintype "input"))
    )
    (net (code "97") (name "Net-(U6B-INB+)") (class "Default")
      (node (ref "C25") (pin "2") (pinfunction "2_2") (pintype "passive"))
      (node (ref "R36") (pin "1") (pinfunction "1_1") (pintype "passive"))
      (node (ref "U6") (pin "5") (pinfunction "INB+_5") (pintype "input"))
    )
    (net (code "98") (name "Net-(U6B-INB-)") (class "Default")
      (node (ref "R32") (pin "2") (pinfunction "2_2") (pintype "passive"))
      (node (ref "U6") (pin "6") (pinfunction "INB-_6") (pintype "input"))
      (node (ref "U6") (pin "7") (pinfunction "OUTB_7") (pintype "output"))
    )
    (net (code "99") (name "Net-(U8-BYP)") (class "Default")
      (node (ref "C20") (pin "2") (pinfunction "2_2") (pintype "passive"))
      (node (ref "U8") (pin "2") (pinfunction "BYP_2") (pintype "passive"))
    )
    (net (code "100") (name "Net-(U8-SA0)") (class "Default")
      (node (ref "R37") (pin "2") (pinfunction "2_2") (pintype "passive"))
      (node (ref "U8") (pin "7") (pinfunction "SA0_7") (pintype "passive"))
    )
    (net (code "101") (name "Net-(U9A-INA+)") (class "Default")
      (node (ref "C22") (pin "2") (pinfunction "2_2") (pintype "passive"))
      (node (ref "R33") (pin "1") (pinfunction "1_1") (pintype "passive"))
      (node (ref "U9") (pin "3") (pinfunction "INA+_3") (pintype "input"))
    )
    (net (code "102") (name "Net-(U9A-INA-)") (class "Default")
      (node (ref "R31") (pin "2") (pinfunction "2_2") (pintype "passive"))
      (node (ref "U9") (pin "1") (pinfunction "OUTA_1") (pintype "output"))
      (node (ref "U9") (pin "2") (pinfunction "INA-_2") (pintype "input"))
    )
    (net (code "103") (name "Net-(U9B-INB+)") (class "Default")
      (node (ref "C30") (pin "2") (pinfunction "2_2") (pintype "passive"))
      (node (ref "R41") (pin "1") (pinfunction "1_1") (pintype "passive"))
      (node (ref "U9") (pin "5") (pinfunction "INB+_5") (pintype "input"))
    )
    (net (code "104") (name "Net-(U9B-INB-)") (class "Default")
      (node (ref "R40") (pin "2") (pinfunction "2_2") (pintype "passive"))
      (node (ref "U9") (pin "6") (pinfunction "INB-_6") (pintype "input"))
      (node (ref "U9") (pin "7") (pinfunction "OUTB_7") (pintype "output"))
    )
    (net (code "105") (name "Net-(U10A-BOOT0)") (class "Default")
      (node (ref "R54") (pin "2") (pinfunction "2_2") (pintype "passive"))
      (node (ref "U10") (pin "60") (pinfunction "BOOT0_60") (pintype "input"))
    )
    (net (code "106") (name "Net-(U10A-NRST)") (class "Default")
      (node (ref "C39") (pin "2") (pinfunction "2_2") (pintype "passive"))
      (node (ref "R57") (pin "2") (pinfunction "2_2") (pintype "passive"))
      (node (ref "S2") (pin "2") (pinfunction "2_2") (pintype "passive"))
      (node (ref "U10") (pin "7") (pinfunction "NRST_7") (pintype "bidirectional"))
    )
    (net (code "107") (name "Net-(U10A-PD0-OSC_IN)") (class "Default")
      (node (ref "C32") (pin "1") (pinfunction "1_1") (pintype "passive"))
      (node (ref "U10") (pin "5") (pinfunction "PD0-OSC_IN_5") (pintype "bidirectional"))
      (node (ref "Y1") (pin "2") (pinfunction "OSC2_2") (pintype "passive"))
    )
    (net (code "108") (name "Net-(U10A-PD1)") (class "Default")
      (node (ref "C33") (pin "1") (pinfunction "1_1") (pintype "passive"))
      (node (ref "U10") (pin "6") (pinfunction "PD1_6") (pintype "bidirectional"))
      (node (ref "Y1") (pin "1") (pinfunction "OSC1_1") (pintype "passive"))
    )
    (net (code "109") (name "Net-(U11A-INA+)") (class "Default")
      (node (ref "R45") (pin "2") (pinfunction "2_2") (pintype "passive"))
      (node (ref "U11") (pin "3") (pinfunction "INA+_3") (pintype "input"))
    )
    (net (code "110") (name "Net-(U11A-INA-)") (class "Default")
      (node (ref "R42") (pin "1") (pinfunction "1_1") (pintype "passive"))
      (node (ref "R44") (pin "2") (pinfunction "2_2") (pintype "passive"))
      (node (ref "U11") (pin "2") (pinfunction "INA-_2") (pintype "input"))
    )
    (net (code "111") (name "Net-(U11B-INB+)") (class "Default")
      (node (ref "R53") (pin "2") (pinfunction "2_2") (pintype "passive"))
      (node (ref "U11") (pin "5") (pinfunction "INB+_5") (pintype "input"))
    )
    (net (code "112") (name "Net-(U11B-INB-)") (class "Default")
      (node (ref "R51") (pin "1") (pinfunction "1_1") (pintype "passive"))
      (node (ref "R52") (pin "2") (pinfunction "2_2") (pintype "passive"))
      (node (ref "U11") (pin "6") (pinfunction "INB-_6") (pintype "input"))
    )
    (net (code "113") (name "Net-(U12A-INA+)") (class "Default")
      (node (ref "C35") (pin "2") (pinfunction "2_2") (pintype "passive"))
      (node (ref "R50") (pin "1") (pinfunction "1_1") (pintype "passive"))
      (node (ref "U12") (pin "3") (pinfunction "INA+_3") (pintype "input"))
    )
    (net (code "114") (name "Net-(U12A-INA-)") (class "Default")
      (node (ref "R49") (pin "2") (pinfunction "2_2") (pintype "passive"))
      (node (ref "U12") (pin "1") (pinfunction "OUTA_1") (pintype "output"))
      (node (ref "U12") (pin "2") (pinfunction "INA-_2") (pintype "input"))
    )
    (net (code "115") (name "Net-(U12B-INB+)") (class "Default")
      (node (ref "C41") (pin "2") (pinfunction "2_2") (pintype "passive"))
      (node (ref "R59") (pin "1") (pinfunction "1_1") (pintype "passive"))
      (node (ref "U12") (pin "5") (pinfunction "INB+_5") (pintype "input"))
    )
    (net (code "116") (name "Net-(U12B-INB-)") (class "Default")
      (node (ref "R58") (pin "2") (pinfunction "2_2") (pintype "passive"))
      (node (ref "U12") (pin "6") (pinfunction "INB-_6") (pintype "input"))
      (node (ref "U12") (pin "7") (pinfunction "OUTB_7") (pintype "output"))
    )
    (net (code "117") (name "Net-(U13-A)") (class "Default")
      (node (ref "R61") (pin "8") (pinfunction "8_8") (pintype "passive"))
      (node (ref "U13") (pin "1") (pinfunction "A_1") (pintype "passive"))
    )
    (net (code "118") (name "Net-(U13-C)") (class "Default")
      (node (ref "R60") (pin "1") (pinfunction "1_1") (pintype "passive"))
      (node (ref "U13") (pin "4") (pinfunction "C_4") (pintype "passive"))
    )
    (net (code "119") (name "Net-(U14-A)") (class "Default")
      (node (ref "R61") (pin "7") (pinfunction "7_7") (pintype "passive"))
      (node (ref "U14") (pin "1") (pinfunction "A_1") (pintype "passive"))
    )
    (net (code "120") (name "Net-(U14-C)") (class "Default")
      (node (ref "R60") (pin "2") (pinfunction "2_2") (pintype "passive"))
      (node (ref "U14") (pin "4") (pinfunction "C_4") (pintype "passive"))
    )
    (net (code "121") (name "Net-(U15-A)") (class "Default")
      (node (ref "R61") (pin "6") (pinfunction "6_6") (pintype "passive"))
      (node (ref "U15") (pin "1") (pinfunction "A_1") (pintype "passive"))
    )
    (net (code "122") (name "Net-(U15-C)") (class "Default")
      (node (ref "R60") (pin "3") (pinfunction "3_3") (pintype "passive"))
      (node (ref "U15") (pin "4") (pinfunction "C_4") (pintype "passive"))
    )
    (net (code "123") (name "Net-(U16-C)") (class "Default")
      (node (ref "R61") (pin "5") (pinfunction "5_5") (pintype "passive"))
      (node (ref "U16") (pin "4") (pinfunction "C_4") (pintype "passive"))
    )
    (net (code "124") (name "Net-(U16-K)") (class "Default")
      (node (ref "R60") (pin "4") (pinfunction "4_4") (pintype "passive"))
      (node (ref "U16") (pin "2") (pinfunction "K_2") (pintype "passive"))
    )
    (net (code "125") (name "Net-(U17-ABD)") (class "Default")
      (node (ref "R8") (pin "2") (pinfunction "2_2") (pintype "passive"))
      (node (ref "U17") (pin "2") (pinfunction "ABD_2") (pintype "passive"))
    )
    (net (code "126") (name "Net-(U17-IN+)") (class "Default")
      (node (ref "R9") (pin "2") (pinfunction "2_2") (pintype "passive"))
      (node (ref "U17") (pin "3") (pinfunction "IN+_3") (pintype "passive"))
    )
    (net (code "127") (name "Net-(U17-IN-)") (class "Default")
      (node (ref "R46") (pin "2") (pinfunction "2_2") (pintype "passive"))
      (node (ref "U17") (pin "4") (pinfunction "IN-_4") (pintype "passive"))
    )
    (net (code "128") (name "Net-(U17-SD)") (class "Default")
      (node (ref "R2") (pin "2") (pinfunction "2_2") (pintype "passive"))
      (node (ref "U17") (pin "1") (pinfunction "SD_1") (pintype "passive"))
    )
    (net (code "129") (name "Net-(U17-VO+)") (class "Default")
      (node (ref "P3") (pin "2") (pinfunction "2_2") (pintype "passive"))
      (node (ref "U17") (pin "6") (pinfunction "VO+_6") (pintype "passive"))
    )
    (net (code "130") (name "Net-(U17-VO-)") (class "Default")
      (node (ref "P3") (pin "1") (pinfunction "1_1") (pintype "passive"))
      (node (ref "U17") (pin "7") (pinfunction "VO-_7") (pintype "passive"))
    )
    (net (code "131") (name "PGND") (class "Default")
      (node (ref "C15") (pin "1") (pinfunction "1_1") (pintype "passive"))
      (node (ref "C16") (pin "1") (pinfunction "1_1") (pintype "passive"))
      (node (ref "C17") (pin "1") (pinfunction "1_1") (pintype "passive"))
      (node (ref "C21") (pin "1") (pinfunction "1_1") (pintype "passive"))
      (node (ref "C22") (pin "1") (pinfunction "1_1") (pintype "passive"))
      (node (ref "C23") (pin "1") (pinfunction "1_1") (pintype "passive"))
      (node (ref "C24") (pin "1") (pinfunction "1_1") (pintype "passive"))
      (node (ref "C25") (pin "1") (pinfunction "1_1") (pintype "passive"))
      (node (ref "C26") (pin "1") (pinfunction "1_1") (pintype "passive"))
      (node (ref "C29") (pin "1") (pinfunction "1_1") (pintype "passive"))
      (node (ref "C3") (pin "1") (pinfunction "1_1") (pintype "passive"))
      (node (ref "C30") (pin "1") (pinfunction "1_1") (pintype "passive"))
      (node (ref "C31") (pin "1") (pinfunction "1_1") (pintype "passive"))
      (node (ref "C34") (pin "1") (pinfunction "1_1") (pintype "passive"))
      (node (ref "C35") (pin "1") (pinfunction "1_1") (pintype "passive"))
      (node (ref "C36") (pin "1") (pinfunction "1_1") (pintype "passive"))
      (node (ref "C40") (pin "1") (pinfunction "1_1") (pintype "passive"))
      (node (ref "C41") (pin "1") (pinfunction "1_1") (pintype "passive"))
      (node (ref "C42") (pin "1") (pinfunction "1_1") (pintype "passive"))
      (node (ref "C45") (pin "2") (pinfunction "2_2") (pintype "passive"))
      (node (ref "C46") (pin "2") (pinfunction "2_2") (pintype "passive"))
      (node (ref "C47") (pin "2") (pinfunction "2_2") (pintype "passive"))
      (node (ref "C49") (pin "2") (pinfunction "2_2") (pintype "passive"))
      (node (ref "C50") (pin "2") (pinfunction "2_2") (pintype "passive"))
      (node (ref "C6") (pin "2") (pinfunction "2_2") (pintype "passive"))
      (node (ref "C7") (pin "2") (pinfunction "2_2") (pintype "passive"))
      (node (ref "C8") (pin "2") (pinfunction "2_2") (pintype "passive"))
      (node (ref "D10") (pin "1") (pinfunction "A_1") (pintype "passive"))
      (node (ref "D11") (pin "1") (pinfunction "A_1") (pintype "passive"))
      (node (ref "D13") (pin "1") (pinfunction "A_1") (pintype "passive"))
      (node (ref "D15") (pin "1") (pinfunction "A_1") (pintype "passive"))
      (node (ref "D17") (pin "1") (pinfunction "A_1") (pintype "passive"))
      (node (ref "D2") (pin "2") (pinfunction "K_2") (pintype "passive"))
      (node (ref "D4") (pin "1") (pinfunction "A_1") (pintype "passive"))
      (node (ref "D7") (pin "1") (pinfunction "A_1") (pintype "passive"))
      (node (ref "P1") (pin "2") (pinfunction "2_2") (pintype "passive"))
      (node (ref "P10") (pin "3") (pinfunction "3_3") (pintype "passive"))
      (node (ref "P11") (pin "3") (pinfunction "3_3") (pintype "passive"))
      (node (ref "P14") (pin "2") (pinfunction "2_2") (pintype "passive"))
      (node (ref "P15") (pin "2") (pinfunction "2_2") (pintype "passive"))
      (node (ref "P5") (pin "3") (pinfunction "3_3") (pintype "passive"))
      (node (ref "P7") (pin "7") (pinfunction "7_7") (pintype "passive"))
      (node (ref "P8") (pin "11") (pinfunction "GND_11") (pintype "passive"))
      (node (ref "P8") (pin "2") (pinfunction "GND_2") (pintype "passive"))
      (node (ref "Q1") (pin "3") (pinfunction "S_3") (pintype "passive"))
      (node (ref "Q3") (pin "3") (pinfunction "S_3") (pintype "passive"))
      (node (ref "Q5") (pin "2") (pinfunction "E_2") (pintype "passive"))
      (node (ref "Q6") (pin "3") (pinfunction "S_3") (pintype "passive"))
      (node (ref "Q8") (pin "3") (pinfunction "S_3") (pintype "passive"))
      (node (ref "R3") (pin "1") (pinfunction "1_1") (pintype "passive"))
      (node (ref "R45") (pin "1") (pinfunction "1_1") (pintype "passive"))
      (node (ref "R5") (pin "2") (pinfunction "2_2") (pintype "passive"))
      (node (ref "R53") (pin "1") (pinfunction "1_1") (pintype "passive"))
      (node (ref "R8") (pin "1") (pinfunction "1_1") (pintype "passive"))
      (node (ref "R9") (pin "1") (pinfunction "1_1") (pintype "passive"))
      (node (ref "U1") (pin "5") (pinfunction "H_5") (pintype "passive"))
      (node (ref "U11") (pin "4") (pinfunction "GND_4") (pintype "power_in"))
      (node (ref "U12") (pin "4") (pinfunction "GND_4") (pintype "power_in"))
      (node (ref "U13") (pin "3") (pinfunction "E_3") (pintype "passive"))
      (node (ref "U14") (pin "3") (pinfunction "E_3") (pintype "passive"))
      (node (ref "U15") (pin "3") (pinfunction "E_3") (pintype "passive"))
      (node (ref "U17") (pin "8") (pinfunction "GND_8") (pintype "passive"))
      (node (ref "U2") (pin "3") (pinfunction "GND_3") (pintype "passive"))
      (node (ref "U3") (pin "3") (pinfunction "GND_3") (pintype "power_in"))
      (node (ref "U3") (pin "5") (pinfunction "~{ON}/OFF_5") (pintype "input"))
      (node (ref "U6") (pin "4") (pinfunction "GND_4") (pintype "power_in"))
      (node (ref "U9") (pin "4") (pinfunction "GND_4") (pintype "power_in"))
    )
    (net (code "132") (name "SGND") (class "Default")
      (node (ref "C10") (pin "2") (pinfunction "2_2") (pintype "passive"))
      (node (ref "C11") (pin "2") (pinfunction "2_2") (pintype "passive"))
      (node (ref "C13") (pin "2") (pinfunction "2_2") (pintype "passive"))
      (node (ref "C14") (pin "2") (pinfunction "2_2") (pintype "passive"))
      (node (ref "C20") (pin "1") (pinfunction "1_1") (pintype "passive"))
      (node (ref "C32") (pin "2") (pinfunction "2_2") (pintype "passive"))
      (node (ref "C33") (pin "2") (pinfunction "2_2") (pintype "passive"))
      (node (ref "C37") (pin "2") (pinfunction "2_2") (pintype "passive"))
      (node (ref "C38") (pin "2") (pinfunction "2_2") (pintype "passive"))
      (node (ref "C39") (pin "1") (pinfunction "1_1") (pintype "passive"))
      (node (ref "C43") (pin "2") (pinfunction "2_2") (pintype "passive"))
      (node (ref "C44") (pin "2") (pinfunction "2_2") (pintype "passive"))
      (node (ref "P12") (pin "4") (pinfunction "4_4") (pintype "passive"))
      (node (ref "P13") (pin "4") (pinfunction "4_4") (pintype "passive"))
      (node (ref "Q2") (pin "2") (pinfunction "E_2") (pintype "passive"))
      (node (ref "Q4") (pin "2") (pinfunction "E_2") (pintype "passive"))
      (node (ref "Q7") (pin "2") (pinfunction "E_2") (pintype "passive"))
      (node (ref "Q9") (pin "2") (pinfunction "E_2") (pintype "passive"))
      (node (ref "R28") (pin "2") (pinfunction "2_2") (pintype "passive"))
      (node (ref "R3") (pin "2") (pinfunction "2_2") (pintype "passive"))
      (node (ref "R37") (pin "1") (pinfunction "1_1") (pintype "passive"))
      (node (ref "R43") (pin "1") (pinfunction "1_1") (pintype "passive"))
      (node (ref "R48") (pin "1") (pinfunction "A0_1") (pintype "passive"))
      (node (ref "R48") (pin "2") (pinfunction "A1_2") (pintype "passive"))
      (node (ref "R48") (pin "3") (pinfunction "A2_3") (pintype "passive"))
      (node (ref "R48") (pin "4") (pinfunction "GND_4") (pintype "passive"))
      (node (ref "R48") (pin "7") (pinfunction "WP_7") (pintype "passive"))
      (node (ref "R54") (pin "1") (pinfunction "1_1") (pintype "passive"))
      (node (ref "S1") (pin "10") (pinfunction "B7_10") (pintype "passive"))
      (node (ref "S1") (pin "11") (pinfunction "B6_11") (pintype "passive"))
      (node (ref "S1") (pin "12") (pinfunction "B5_12") (pintype "passive"))
      (node (ref "S1") (pin "13") (pinfunction "B4_13") (pintype "passive"))
      (node (ref "S1") (pin "14") (pinfunction "B3_14") (pintype "passive"))
      (node (ref "S1") (pin "15") (pinfunction "B2_15") (pintype "passive"))
      (node (ref "S1") (pin "16") (pinfunction "B1_16") (pintype "passive"))
      (node (ref "S1") (pin "9") (pinfunction "B8_9") (pintype "passive"))
      (node (ref "S2") (pin "1") (pinfunction "1_1") (pintype "passive"))
      (node (ref "U10") (pin "12") (pinfunction "VSSA_12") (pintype "power_in"))
      (node (ref "U10") (pin "18") (pinfunction "VSS_4_18") (pintype "power_in"))
      (node (ref "U10") (pin "31") (pinfunction "VSS_1_31") (pintype "power_in"))
      (node (ref "U10") (pin "47") (pinfunction "VSS_2_47") (pintype "power_in"))
      (node (ref "U10") (pin "63") (pinfunction "VSS_3_63") (pintype "power_in"))
      (node (ref "U13") (pin "2") (pinfunction "K_2") (pintype "passive"))
      (node (ref "U14") (pin "2") (pinfunction "K_2") (pintype "passive"))
      (node (ref "U15") (pin "2") (pinfunction "K_2") (pintype "passive"))
      (node (ref "U16") (pin "3") (pinfunction "E_3") (pintype "passive"))
      (node (ref "U4") (pin "1") (pinfunction "Ground_1") (pintype "passive"))
      (node (ref "U5") (pin "9") (pinfunction "GND_9") (pintype "passive"))
      (node (ref "U7") (pin "1") (pinfunction "GND_1") (pintype "passive"))
      (node (ref "U8") (pin "10") (pinfunction "GND_10") (pintype "passive"))
      (node (ref "U8") (pin "12") (pinfunction "GND_12") (pintype "passive"))
      (node (ref "U8") (pin "5") (pinfunction "GND_5") (pintype "passive"))
    )
    (net (code "133") (name "unconnected-(P7-Pad6)") (class "Default")
      (node (ref "P7") (pin "6") (pinfunction "6_6") (pintype "passive+no_connect"))
    )
    (net (code "134") (name "unconnected-(P8-ANT-Pad1)") (class "Default")
      (node (ref "P8") (pin "1") (pinfunction "ANT_1") (pintype "passive+no_connect"))
    )
    (net (code "135") (name "unconnected-(P8-D3-Pad9)") (class "Default")
      (node (ref "P8") (pin "9") (pinfunction "D3_9") (pintype "passive+no_connect"))
    )
    (net (code "136") (name "unconnected-(P8-VT-Pad5)") (class "Default")
      (node (ref "P8") (pin "5") (pinfunction "VT_5") (pintype "passive+no_connect"))
    )
    (net (code "137") (name "unconnected-(U1-A-Pad3)") (class "Default")
      (node (ref "U1") (pin "3") (pinfunction "A_3") (pintype "passive+no_connect"))
    )
    (net (code "138") (name "unconnected-(U1-B-Pad4)") (class "Default")
      (node (ref "U1") (pin "4") (pinfunction "B_4") (pintype "passive+no_connect"))
    )
    (net (code "139") (name "unconnected-(U2-VIN2-Pad8)") (class "Default")
      (node (ref "U2") (pin "8") (pinfunction "VIN2_8") (pintype "passive+no_connect"))
    )
    (net (code "140") (name "unconnected-(U2-VOUT2-Pad7)") (class "Default")
      (node (ref "U2") (pin "7") (pinfunction "VOUT2_7") (pintype "passive+no_connect"))
    )
    (net (code "141") (name "unconnected-(U3-TAB-Pad6)") (class "Default")
      (node (ref "U3") (pin "6") (pinfunction "TAB_6") (pintype "power_in+no_connect"))
    )
    (net (code "142") (name "unconnected-(U5-ADC-Pad2)") (class "Default")
      (node (ref "U5") (pin "2") (pinfunction "ADC_2") (pintype "passive+no_connect"))
    )
    (net (code "143") (name "unconnected-(U5-GPIO0-Pad12)") (class "Default")
      (node (ref "U5") (pin "12") (pinfunction "GPIO0_12") (pintype "passive+no_connect"))
    )
    (net (code "144") (name "unconnected-(U5-GPIO2-Pad11)") (class "Default")
      (node (ref "U5") (pin "11") (pinfunction "GPIO2_11") (pintype "passive+no_connect"))
    )
    (net (code "145") (name "unconnected-(U5-GPIO4-Pad14)") (class "Default")
      (node (ref "U5") (pin "14") (pinfunction "GPIO4_14") (pintype "passive+no_connect"))
    )
    (net (code "146") (name "unconnected-(U5-GPIO5-Pad13)") (class "Default")
      (node (ref "U5") (pin "13") (pinfunction "GPIO5_13") (pintype "passive+no_connect"))
    )
    (net (code "147") (name "unconnected-(U5-GPIO12-Pad6)") (class "Default")
      (node (ref "U5") (pin "6") (pinfunction "GPIO12_6") (pintype "passive+no_connect"))
    )
    (net (code "148") (name "unconnected-(U5-GPIO13-Pad7)") (class "Default")
      (node (ref "U5") (pin "7") (pinfunction "GPIO13_7") (pintype "passive+no_connect"))
    )
    (net (code "149") (name "unconnected-(U5-GPIO14-Pad5)") (class "Default")
      (node (ref "U5") (pin "5") (pinfunction "GPIO14_5") (pintype "passive+no_connect"))
    )
    (net (code "150") (name "unconnected-(U5-GPIO16-Pad4)") (class "Default")
      (node (ref "U5") (pin "4") (pinfunction "GPIO16_4") (pintype "passive+no_connect"))
    )
    (net (code "151") (name "unconnected-(U8-INT1-Pad11)") (class "Default")
      (node (ref "U8") (pin "11") (pinfunction "INT1_11") (pintype "passive+no_connect"))
    )
    (net (code "152") (name "unconnected-(U8-INT2-Pad9)") (class "Default")
      (node (ref "U8") (pin "9") (pinfunction "INT2_9") (pintype "passive+no_connect"))
    )
    (net (code "153") (name "unconnected-(U8-NC-Pad3)") (class "Default")
      (node (ref "U8") (pin "3") (pinfunction "NC_3") (pintype "passive"))
    )
    (net (code "154") (name "unconnected-(U8-NC-Pad8)") (class "Default")
      (node (ref "U8") (pin "8") (pinfunction "NC_8") (pintype "passive"))
    )
    (net (code "155") (name "unconnected-(U8-NC-Pad13)") (class "Default")
      (node (ref "U8") (pin "13") (pinfunction "NC_13") (pintype "passive"))
    )
    (net (code "156") (name "unconnected-(U8-NC-Pad15)") (class "Default")
      (node (ref "U8") (pin "15") (pinfunction "NC_15") (pintype "passive"))
    )
    (net (code "157") (name "unconnected-(U8-NC-Pad16)") (class "Default")
      (node (ref "U8") (pin "16") (pinfunction "NC_16") (pintype "passive"))
    )
    (net (code "158") (name "unconnected-(U10A-PC13-TAMPER-RTC-Pad2)") (class "Default")
      (node (ref "U10") (pin "2") (pinfunction "PC13-TAMPER-RTC_2") (pintype "bidirectional+no_connect"))
    )
    (net (code "159") (name "unconnected-(U10A-PC14-OSC32_IN-Pad3)") (class "Default")
      (node (ref "U10") (pin "3") (pinfunction "PC14-OSC32_IN_3") (pintype "bidirectional+no_connect"))
    )
    (net (code "160") (name "unconnected-(U10A-PC15-OSC32_OUT-Pad4)") (class "Default")
      (node (ref "U10") (pin "4") (pinfunction "PC15-OSC32_OUT_4") (pintype "bidirectional+no_connect"))
    )
    (net (code "161") (name "unconnected-(U10B-VBAT-Pad1)") (class "Default")
      (node (ref "U10") (pin "1") (pinfunction "VBAT_1") (pintype "power_in+no_connect"))
    )
  )
)
